# A-14732-40009.net
KiCad netlist of a schematic drawn in EAGLE
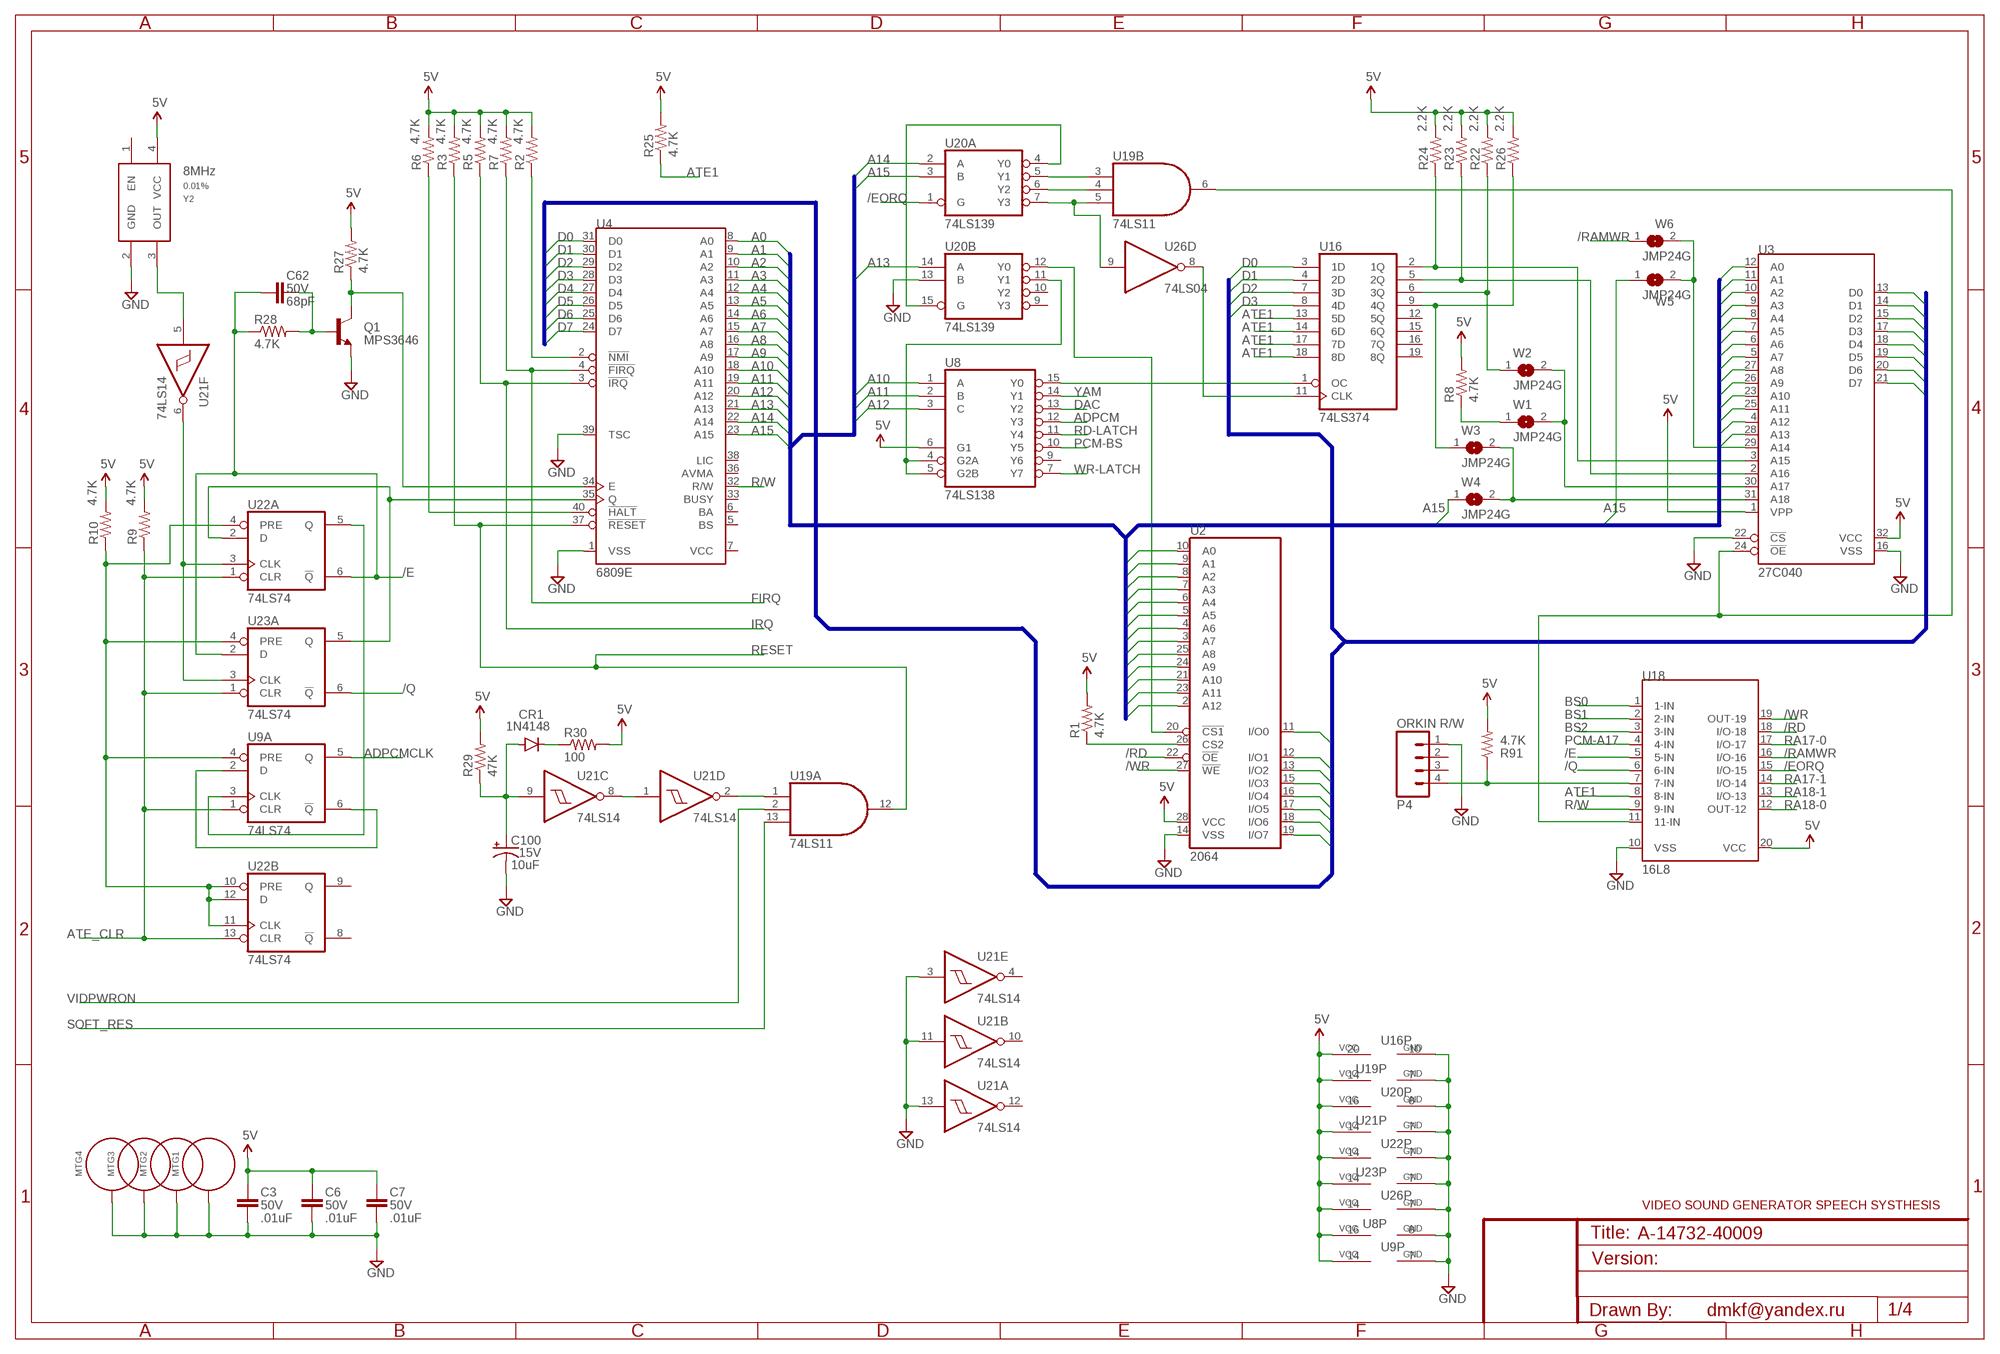
[diagram p0: schematic, sheet 1]
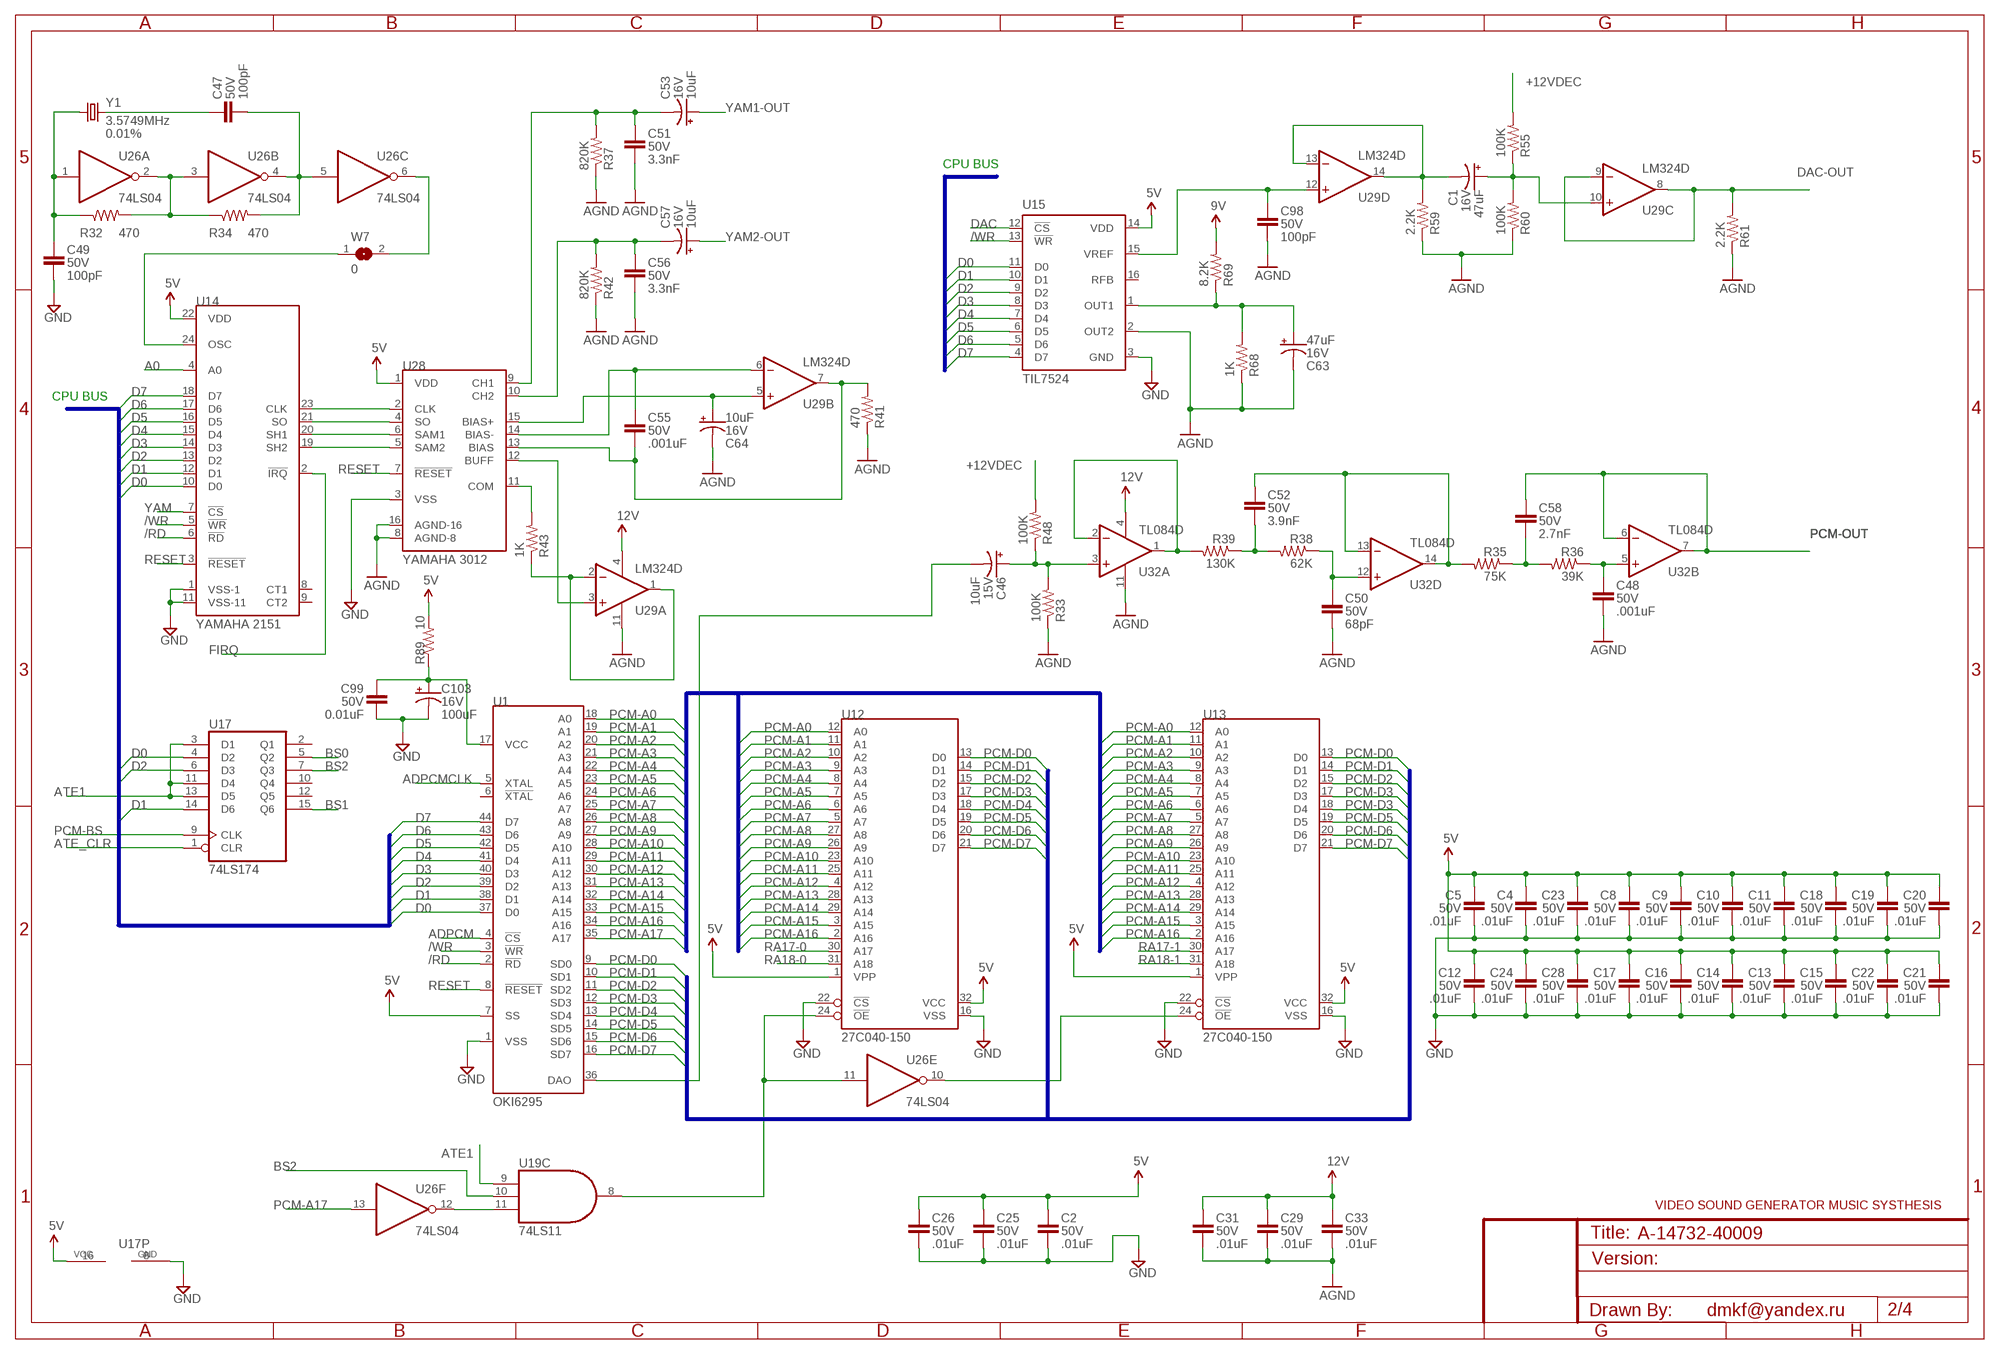
[diagram p1: schematic, sheet 2]
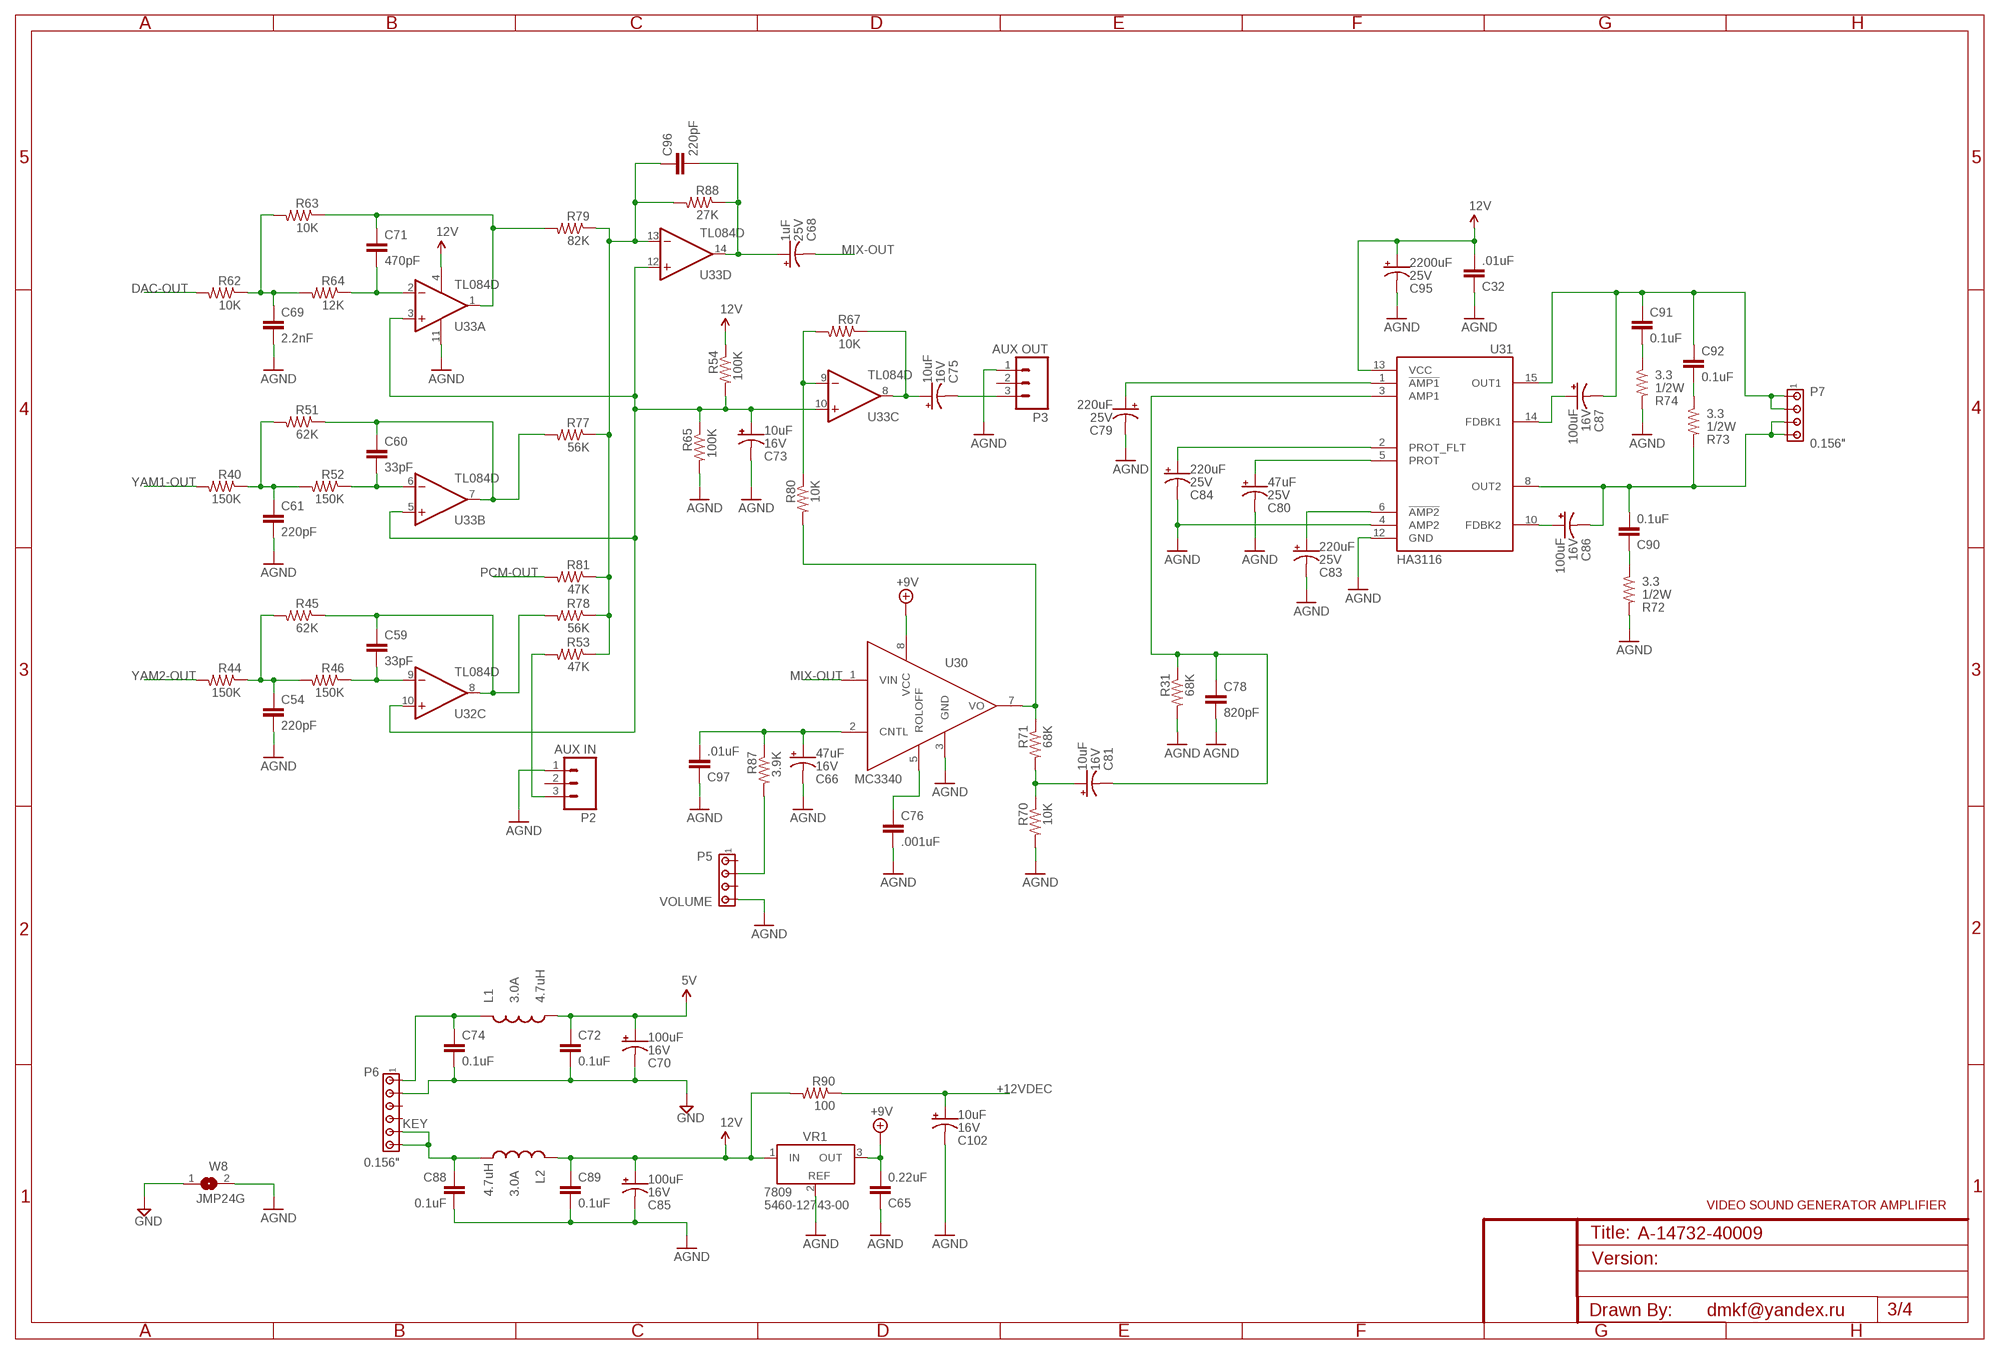
[diagram p2: schematic, sheet 3]
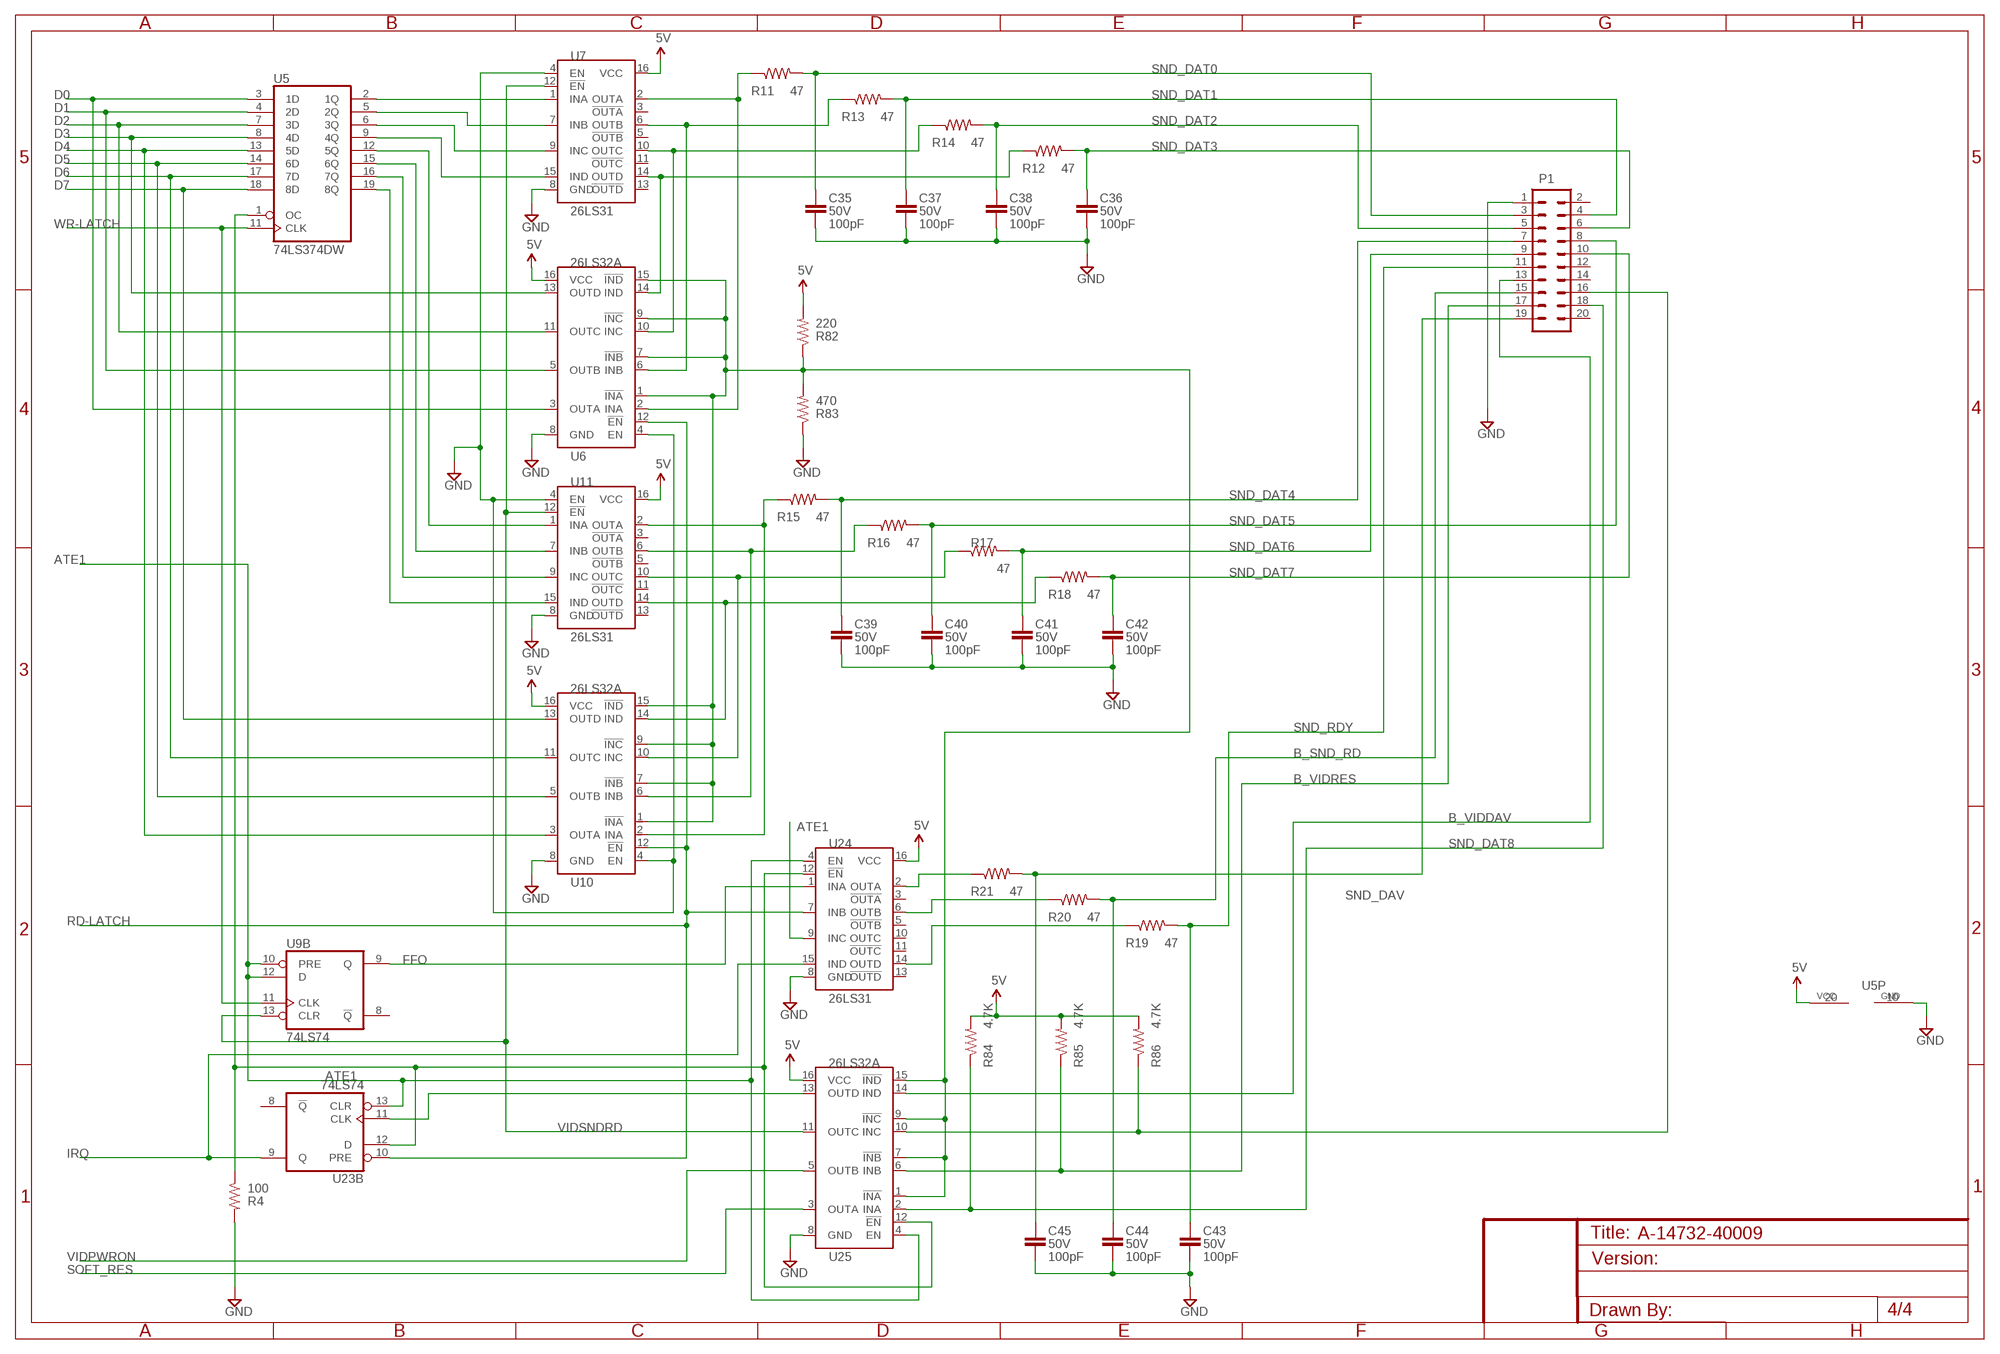
[diagram p3: schematic, sheet 4]

(export (version "E")
  (design (tool "Eeschema 10.0.6"))
  (components
    (comp (ref "C3")
      (value ".01uF")
      (footprint "eagle-import:1206-CAP")
      (fields (field (name "VOLTAGE") "50V"))
      (libsource (lib "eagle-import") (part "1.0UF50V10%(1206)"))
    )
    (comp (ref "C6")
      (value ".01uF")
      (footprint "eagle-import:1206-CAP")
      (fields (field (name "VOLTAGE") "50V"))
      (libsource (lib "eagle-import") (part "1.0UF50V10%(1206)"))
    )
    (comp (ref "C7")
      (value ".01uF")
      (footprint "eagle-import:1206-CAP")
      (fields (field (name "VOLTAGE") "50V"))
      (libsource (lib "eagle-import") (part "1.0UF50V10%(1206)"))
    )
    (comp (ref "C62")
      (value "68pF")
      (footprint "eagle-import:1206-CAP")
      (libsource (lib "eagle-import") (part "1.0UF50V10%(1206)"))
    )
    (comp (ref "C100")
      (value "10uF")
      (footprint "eagle-import:EIA3216")
      (libsource (lib "eagle-import") (part "10UF-16V-10%(TANT)"))
    )
    (comp (ref "CR1")
      (value "1N4148")
      (footprint "eagle-import:SMA-DIODE")
      (libsource (lib "eagle-import") (part "DIODESMA"))
    )
    (comp (ref "MTG1")
      (value "MTGHOLE")
      (footprint "eagle-import:STANDOFF-ELECTRICAL")
      (libsource (lib "eagle-import") (part "STANDOFF_ELECTRICAL"))
    )
    (comp (ref "MTG2")
      (value "MTGHOLE")
      (footprint "eagle-import:STANDOFF-ELECTRICAL")
      (libsource (lib "eagle-import") (part "STANDOFF_ELECTRICAL"))
    )
    (comp (ref "MTG3")
      (value "MTGHOLE")
      (footprint "eagle-import:STANDOFF-ELECTRICAL")
      (libsource (lib "eagle-import") (part "STANDOFF_ELECTRICAL"))
    )
    (comp (ref "MTG4")
      (value "MTGHOLE")
      (footprint "eagle-import:STANDOFF-ELECTRICAL")
      (libsource (lib "eagle-import") (part "STANDOFF_ELECTRICAL"))
    )
    (comp (ref "P4")
      (value "ORKIN R/W")
      (footprint "eagle-import:1X04_LONGPADS")
      (libsource (lib "eagle-import") (part "M04LONGPADS"))
    )
    (comp (ref "Q1")
      (value "MPS3646")
      (footprint "eagle-import:SOT23-3")
      (libsource (lib "eagle-import") (part "TRANSISTOR_NPNMMBT2222A"))
    )
    (comp (ref "R1")
      (value "4.7K")
      (footprint "eagle-import:R1206")
      (libsource (lib "eagle-import") (part "R-US_R1206"))
    )
    (comp (ref "R2")
      (value "4.7K")
      (footprint "eagle-import:R1206")
      (libsource (lib "eagle-import") (part "R-US_R1206"))
    )
    (comp (ref "R3")
      (value "4.7K")
      (footprint "eagle-import:R1206")
      (libsource (lib "eagle-import") (part "R-US_R1206"))
    )
    (comp (ref "R5")
      (value "4.7K")
      (footprint "eagle-import:R1206")
      (libsource (lib "eagle-import") (part "R-US_R1206"))
    )
    (comp (ref "R6")
      (value "4.7K")
      (footprint "eagle-import:R1206")
      (libsource (lib "eagle-import") (part "R-US_R1206"))
    )
    (comp (ref "R7")
      (value "4.7K")
      (footprint "eagle-import:R1206")
      (libsource (lib "eagle-import") (part "R-US_R1206"))
    )
    (comp (ref "R8")
      (value "4.7K")
      (footprint "eagle-import:R1206")
      (libsource (lib "eagle-import") (part "R-US_R1206"))
    )
    (comp (ref "R9")
      (value "4.7K")
      (footprint "eagle-import:R1206")
      (libsource (lib "eagle-import") (part "R-US_R1206"))
    )
    (comp (ref "R10")
      (value "4.7K")
      (footprint "eagle-import:R1206")
      (libsource (lib "eagle-import") (part "R-US_R1206"))
    )
    (comp (ref "R22")
      (value "2.2K")
      (footprint "eagle-import:R1206")
      (libsource (lib "eagle-import") (part "R-US_R1206"))
    )
    (comp (ref "R23")
      (value "2.2K")
      (footprint "eagle-import:R1206")
      (libsource (lib "eagle-import") (part "R-US_R1206"))
    )
    (comp (ref "R24")
      (value "2.2K")
      (footprint "eagle-import:R1206")
      (libsource (lib "eagle-import") (part "R-US_R1206"))
    )
    (comp (ref "R25")
      (value "4.7K")
      (footprint "eagle-import:R1206")
      (libsource (lib "eagle-import") (part "R-US_R1206"))
    )
    (comp (ref "R26")
      (value "2.2K")
      (footprint "eagle-import:R1206")
      (libsource (lib "eagle-import") (part "R-US_R1206"))
    )
    (comp (ref "R27")
      (value "4.7K")
      (footprint "eagle-import:R1206")
      (libsource (lib "eagle-import") (part "R-US_R1206"))
    )
    (comp (ref "R28")
      (value "4.7K")
      (footprint "eagle-import:R1206")
      (libsource (lib "eagle-import") (part "R-US_R1206"))
    )
    (comp (ref "R29")
      (value "47K")
      (footprint "eagle-import:R1206")
      (libsource (lib "eagle-import") (part "R-US_R1206"))
    )
    (comp (ref "R30")
      (value "100")
      (footprint "eagle-import:R1206")
      (libsource (lib "eagle-import") (part "R-US_R1206"))
    )
    (comp (ref "R91")
      (value "4.7K")
      (footprint "eagle-import:R1206")
      (libsource (lib "eagle-import") (part "R-US_R1206"))
    )
    (comp (ref "U2")
      (value "2064")
      (footprint "eagle-import:MS6264L")
      (libsource (lib "eagle-import") (part "MS6264L"))
    )
    (comp (ref "U3")
      (value "27C040")
      (footprint "eagle-import:27C040")
      (libsource (lib "eagle-import") (part "27C040"))
    )
    (comp (ref "U4")
      (value "6809E")
      (footprint "eagle-import:6809E")
      (libsource (lib "eagle-import") (part "6809E"))
    )
    (comp (ref "U8")
      (value "74LS138")
      (footprint "eagle-import:SO16")
      (libsource (lib "eagle-import") (part "74138DLS"))
    )
    (comp (ref "U9")
      (value "74LS74")
      (footprint "eagle-import:SO14")
      (libsource (lib "eagle-import") (part "7474DLS"))
    )
    (comp (ref "U16")
      (value "74LS374")
      (footprint "eagle-import:SO20W")
      (libsource (lib "eagle-import") (part "74374DWLS"))
    )
    (comp (ref "U18")
      (value "16L8")
      (footprint "eagle-import:16L8")
      (libsource (lib "eagle-import") (part "PAL16L8"))
    )
    (comp (ref "U19")
      (value "74LS11")
      (footprint "eagle-import:SO14")
      (libsource (lib "eagle-import") (part "7411DLS"))
    )
    (comp (ref "U20")
      (value "74LS139")
      (footprint "eagle-import:SO16")
      (libsource (lib "eagle-import") (part "74139DLS"))
    )
    (comp (ref "U21")
      (value "74LS14")
      (footprint "eagle-import:SO14")
      (libsource (lib "eagle-import") (part "7414DLS"))
    )
    (comp (ref "U22")
      (value "74LS74")
      (footprint "eagle-import:SO14")
      (libsource (lib "eagle-import") (part "7474DLS"))
    )
    (comp (ref "U23")
      (value "74LS74")
      (footprint "eagle-import:SO14")
      (libsource (lib "eagle-import") (part "7474DLS"))
    )
    (comp (ref "U26")
      (value "74LS04")
      (footprint "eagle-import:SO14")
      (libsource (lib "eagle-import") (part "7404DLS"))
    )
    (comp (ref "W1")
      (value "JMP24G")
      (footprint "eagle-import:SJ")
      (libsource (lib "eagle-import") (part "SJ"))
    )
    (comp (ref "W2")
      (value "JMP24G")
      (footprint "eagle-import:SJ")
      (libsource (lib "eagle-import") (part "SJ"))
    )
    (comp (ref "W3")
      (value "JMP24G")
      (footprint "eagle-import:SJ")
      (libsource (lib "eagle-import") (part "SJ"))
    )
    (comp (ref "W4")
      (value "JMP24G")
      (footprint "eagle-import:SJ")
      (libsource (lib "eagle-import") (part "SJ"))
    )
    (comp (ref "W5")
      (value "JMP24G")
      (footprint "eagle-import:SJ")
      (libsource (lib "eagle-import") (part "SJ"))
    )
    (comp (ref "W6")
      (value "JMP24G")
      (footprint "eagle-import:SJ")
      (libsource (lib "eagle-import") (part "SJ"))
    )
    (comp (ref "Y2")
      (value "8MHz")
      (footprint "eagle-import:CRYSTAL-OSC-SMD-5X3")
      (fields (field (name "TOLERANCE") "0.01%"))
      (libsource (lib "eagle-import") (part "OSCILLATOR5X3-PIN1-INDICATED"))
    )
    (comp (ref "C32")
      (value ".01uF")
      (footprint "eagle-import:1206-CAP")
      (fields (field (name "VOLTAGE") "50V"))
      (libsource (lib "eagle-import") (part "1.0UF50V10%(1206)"))
    )
    (comp (ref "C54")
      (value "220pF")
      (footprint "eagle-import:1206-CAP")
      (fields (field (name "VOLTAGE") "50V"))
      (libsource (lib "eagle-import") (part "1.0UF50V10%(1206)"))
    )
    (comp (ref "C59")
      (value "33pF")
      (footprint "eagle-import:1206-CAP")
      (fields (field (name "VOLTAGE") "50V"))
      (libsource (lib "eagle-import") (part "1.0UF50V10%(1206)"))
    )
    (comp (ref "C60")
      (value "33pF")
      (footprint "eagle-import:1206-CAP")
      (fields (field (name "VOLTAGE") "50V"))
      (libsource (lib "eagle-import") (part "1.0UF50V10%(1206)"))
    )
    (comp (ref "C61")
      (value "220pF")
      (footprint "eagle-import:1206-CAP")
      (fields (field (name "VOLTAGE") "50V"))
      (libsource (lib "eagle-import") (part "1.0UF50V10%(1206)"))
    )
    (comp (ref "C65")
      (value "0.22uF")
      (footprint "eagle-import:0805-CAP")
      (fields (field (name "VOLTAGE") "50V"))
      (libsource (lib "eagle-import") (part "0.33UF-50V-10%(0805)"))
    )
    (comp (ref "C66")
      (value "47uF")
      (footprint "eagle-import:NIC_10X10.5_CAP")
      (fields (field (name "VOLTAGE") "16V"))
      (libsource (lib "eagle-import") (part "100UF-63V-20%(ELECT)"))
    )
    (comp (ref "C68")
      (value "1uF")
      (footprint "eagle-import:NIC_10X10.5_CAP")
      (fields (field (name "VOLTAGE") "25V"))
      (libsource (lib "eagle-import") (part "100UF-63V-20%(ELECT)"))
    )
    (comp (ref "C69")
      (value "2.2nF")
      (footprint "eagle-import:1206-CAP")
      (fields (field (name "VOLTAGE") "50V"))
      (libsource (lib "eagle-import") (part "1.0UF50V10%(1206)"))
    )
    (comp (ref "C70")
      (value "100uF")
      (footprint "eagle-import:NIC_10X10.5_CAP")
      (fields (field (name "VOLTAGE") "16V"))
      (libsource (lib "eagle-import") (part "100UF-63V-20%(ELECT)"))
    )
    (comp (ref "C71")
      (value "470pF")
      (footprint "eagle-import:1206-CAP")
      (fields (field (name "VOLTAGE") "50V"))
      (libsource (lib "eagle-import") (part "1.0UF50V10%(1206)"))
    )
    (comp (ref "C72")
      (value "0.1uF")
      (footprint "eagle-import:1206-CAP")
      (fields (field (name "VOLTAGE") "50V"))
      (libsource (lib "eagle-import") (part "1.0UF50V10%(1206)"))
    )
    (comp (ref "C73")
      (value "10uF")
      (footprint "eagle-import:NIC_10X10.5_CAP")
      (fields (field (name "VOLTAGE") "16V"))
      (libsource (lib "eagle-import") (part "100UF-63V-20%(ELECT)"))
    )
    (comp (ref "C74")
      (value "0.1uF")
      (footprint "eagle-import:1206-CAP")
      (fields (field (name "VOLTAGE") "50V"))
      (libsource (lib "eagle-import") (part "1.0UF50V10%(1206)"))
    )
    (comp (ref "C75")
      (value "10uF")
      (footprint "eagle-import:NIC_10X10.5_CAP")
      (fields (field (name "VOLTAGE") "16V"))
      (libsource (lib "eagle-import") (part "100UF-63V-20%(ELECT)"))
    )
    (comp (ref "C76")
      (value ".001uF")
      (footprint "eagle-import:1206-CAP")
      (fields (field (name "VOLTAGE") "50V"))
      (libsource (lib "eagle-import") (part "1.0UF50V10%(1206)"))
    )
    (comp (ref "C78")
      (value "820pF")
      (footprint "eagle-import:1206-CAP")
      (fields (field (name "VOLTAGE") "50V"))
      (libsource (lib "eagle-import") (part "1.0UF50V10%(1206)"))
    )
    (comp (ref "C79")
      (value "220uF")
      (footprint "eagle-import:NIC_10X10.5_CAP")
      (fields (field (name "VOLTAGE") "25V"))
      (libsource (lib "eagle-import") (part "100UF-63V-20%(ELECT)"))
    )
    (comp (ref "C80")
      (value "47uF")
      (footprint "eagle-import:NIC_10X10.5_CAP")
      (fields (field (name "VOLTAGE") "25V"))
      (libsource (lib "eagle-import") (part "100UF-63V-20%(ELECT)"))
    )
    (comp (ref "C81")
      (value "10uF")
      (footprint "eagle-import:NIC_10X10.5_CAP")
      (fields (field (name "VOLTAGE") "16V"))
      (libsource (lib "eagle-import") (part "100UF-63V-20%(ELECT)"))
    )
    (comp (ref "C83")
      (value "220uF")
      (footprint "eagle-import:NIC_10X10.5_CAP")
      (fields (field (name "VOLTAGE") "25V"))
      (libsource (lib "eagle-import") (part "100UF-63V-20%(ELECT)"))
    )
    (comp (ref "C84")
      (value "220uF")
      (footprint "eagle-import:NIC_10X10.5_CAP")
      (fields (field (name "VOLTAGE") "25V"))
      (libsource (lib "eagle-import") (part "100UF-63V-20%(ELECT)"))
    )
    (comp (ref "C85")
      (value "100uF")
      (footprint "eagle-import:NIC_10X10.5_CAP")
      (fields (field (name "VOLTAGE") "16V"))
      (libsource (lib "eagle-import") (part "100UF-63V-20%(ELECT)"))
    )
    (comp (ref "C86")
      (value "100uF")
      (footprint "eagle-import:NIC_10X10.5_CAP")
      (fields (field (name "VOLTAGE") "16V"))
      (libsource (lib "eagle-import") (part "100UF-63V-20%(ELECT)"))
    )
    (comp (ref "C87")
      (value "100uF")
      (footprint "eagle-import:NIC_10X10.5_CAP")
      (fields (field (name "VOLTAGE") "16V"))
      (libsource (lib "eagle-import") (part "100UF-63V-20%(ELECT)"))
    )
    (comp (ref "C88")
      (value "0.1uF")
      (footprint "eagle-import:1206-CAP")
      (fields (field (name "VOLTAGE") "50V"))
      (libsource (lib "eagle-import") (part "1.0UF50V10%(1206)"))
    )
    (comp (ref "C89")
      (value "0.1uF")
      (footprint "eagle-import:1206-CAP")
      (fields (field (name "VOLTAGE") "50V"))
      (libsource (lib "eagle-import") (part "1.0UF50V10%(1206)"))
    )
    (comp (ref "C90")
      (value "0.1uF")
      (footprint "eagle-import:1206-CAP")
      (fields (field (name "VOLTAGE") "50V"))
      (libsource (lib "eagle-import") (part "1.0UF50V10%(1206)"))
    )
    (comp (ref "C91")
      (value "0.1uF")
      (footprint "eagle-import:1206-CAP")
      (fields (field (name "VOLTAGE") "50V"))
      (libsource (lib "eagle-import") (part "1.0UF50V10%(1206)"))
    )
    (comp (ref "C92")
      (value "0.1uF")
      (footprint "eagle-import:1206-CAP")
      (fields (field (name "VOLTAGE") "50V"))
      (libsource (lib "eagle-import") (part "1.0UF50V10%(1206)"))
    )
    (comp (ref "C95")
      (value "2200uF")
      (footprint "eagle-import:NIC_10X10.5_CAP")
      (fields (field (name "VOLTAGE") "25V"))
      (libsource (lib "eagle-import") (part "100UF-63V-20%(ELECT)"))
    )
    (comp (ref "C96")
      (value "220pF")
      (footprint "eagle-import:1206-CAP")
      (fields (field (name "VOLTAGE") "50V"))
      (libsource (lib "eagle-import") (part "1.0UF50V10%(1206)"))
    )
    (comp (ref "C97")
      (value ".01uF")
      (footprint "eagle-import:1206-CAP")
      (fields (field (name "VOLTAGE") "50V"))
      (libsource (lib "eagle-import") (part "1.0UF50V10%(1206)"))
    )
    (comp (ref "C102")
      (value "10uF")
      (footprint "eagle-import:NIC_10X10.5_CAP")
      (fields (field (name "VOLTAGE") "16V"))
      (libsource (lib "eagle-import") (part "100UF-63V-20%(ELECT)"))
    )
    (comp (ref "L1")
      (value "4.7uH")
      (footprint "eagle-import:NPI75C")
      (fields (field (name "CUR") "3.0A"))
      (libsource (lib "eagle-import") (part "INDUCTORNPI75"))
    )
    (comp (ref "L2")
      (value "4.7uH")
      (footprint "eagle-import:NPI75C")
      (fields (field (name "CURRENT") "3.0A"))
      (libsource (lib "eagle-import") (part "INDUCTORNPI75"))
    )
    (comp (ref "P2")
      (value "AUX IN")
      (footprint "eagle-import:1X03_LONGPADS")
      (libsource (lib "eagle-import") (part "M03LONGPADS"))
    )
    (comp (ref "P3")
      (value "AUX OUT")
      (footprint "eagle-import:1X03_LONGPADS")
      (libsource (lib "eagle-import") (part "M03LONGPADS"))
    )
    (comp (ref "P5")
      (value "VOLUME")
      (footprint "eagle-import:1X4MTA")
      (libsource (lib "eagle-import") (part "MTA04-156"))
    )
    (comp (ref "P6")
      (value "0.156\"")
      (footprint "eagle-import:1X6MTA")
      (libsource (lib "eagle-import") (part "MTA06-156"))
    )
    (comp (ref "P7")
      (value "0.156\"")
      (footprint "eagle-import:1X4MTA")
      (libsource (lib "eagle-import") (part "MTA04-156"))
    )
    (comp (ref "R31")
      (value "68K")
      (footprint "eagle-import:R1206")
      (libsource (lib "eagle-import") (part "R-US_R1206"))
    )
    (comp (ref "R40")
      (value "150K")
      (footprint "eagle-import:R1206")
      (libsource (lib "eagle-import") (part "R-US_R1206"))
    )
    (comp (ref "R44")
      (value "150K")
      (footprint "eagle-import:R1206")
      (libsource (lib "eagle-import") (part "R-US_R1206"))
    )
    (comp (ref "R45")
      (value "62K")
      (footprint "eagle-import:R1206")
      (libsource (lib "eagle-import") (part "R-US_R1206"))
    )
    (comp (ref "R46")
      (value "150K")
      (footprint "eagle-import:R1206")
      (libsource (lib "eagle-import") (part "R-US_R1206"))
    )
    (comp (ref "R51")
      (value "62K")
      (footprint "eagle-import:R1206")
      (libsource (lib "eagle-import") (part "R-US_R1206"))
    )
    (comp (ref "R52")
      (value "150K")
      (footprint "eagle-import:R1206")
      (libsource (lib "eagle-import") (part "R-US_R1206"))
    )
    (comp (ref "R53")
      (value "47K")
      (footprint "eagle-import:R1206")
      (libsource (lib "eagle-import") (part "R-US_R1206"))
    )
    (comp (ref "R54")
      (value "100K")
      (footprint "eagle-import:R1206")
      (libsource (lib "eagle-import") (part "R-US_R1206"))
    )
    (comp (ref "R62")
      (value "10K")
      (footprint "eagle-import:R1206")
      (libsource (lib "eagle-import") (part "R-US_R1206"))
    )
    (comp (ref "R63")
      (value "10K")
      (footprint "eagle-import:R1206")
      (libsource (lib "eagle-import") (part "R-US_R1206"))
    )
    (comp (ref "R64")
      (value "12K")
      (footprint "eagle-import:R1206")
      (libsource (lib "eagle-import") (part "R-US_R1206"))
    )
    (comp (ref "R65")
      (value "100K")
      (footprint "eagle-import:R1206")
      (libsource (lib "eagle-import") (part "R-US_R1206"))
    )
    (comp (ref "R67")
      (value "10K")
      (footprint "eagle-import:R1206")
      (libsource (lib "eagle-import") (part "R-US_R1206"))
    )
    (comp (ref "R70")
      (value "10K")
      (footprint "eagle-import:R1206")
      (libsource (lib "eagle-import") (part "R-US_R1206"))
    )
    (comp (ref "R71")
      (value "68K")
      (footprint "eagle-import:R1206")
      (libsource (lib "eagle-import") (part "R-US_R1206"))
    )
    (comp (ref "R72")
      (value "3.3")
      (footprint "eagle-import:R1206")
      (fields (field (name "POWER") "1/2W"))
      (libsource (lib "eagle-import") (part "R-US_R1206"))
    )
    (comp (ref "R73")
      (value "3.3")
      (footprint "eagle-import:R1206")
      (fields (field (name "POWER") "1/2W"))
      (libsource (lib "eagle-import") (part "R-US_R1206"))
    )
    (comp (ref "R74")
      (value "3.3")
      (footprint "eagle-import:R1206")
      (fields (field (name "POWER") "1/2W"))
      (libsource (lib "eagle-import") (part "R-US_R1206"))
    )
    (comp (ref "R77")
      (value "56K")
      (footprint "eagle-import:R1206")
      (libsource (lib "eagle-import") (part "R-US_R1206"))
    )
    (comp (ref "R78")
      (value "56K")
      (footprint "eagle-import:R1206")
      (libsource (lib "eagle-import") (part "R-US_R1206"))
    )
    (comp (ref "R79")
      (value "82K")
      (footprint "eagle-import:R1206")
      (libsource (lib "eagle-import") (part "R-US_R1206"))
    )
    (comp (ref "R80")
      (value "10K")
      (footprint "eagle-import:R1206")
      (libsource (lib "eagle-import") (part "R-US_R1206"))
    )
    (comp (ref "R81")
      (value "47K")
      (footprint "eagle-import:R1206")
      (libsource (lib "eagle-import") (part "R-US_R1206"))
    )
    (comp (ref "R87")
      (value "3.9K")
      (footprint "eagle-import:R1206")
      (libsource (lib "eagle-import") (part "R-US_R1206"))
    )
    (comp (ref "R88")
      (value "27K")
      (footprint "eagle-import:R1206")
      (libsource (lib "eagle-import") (part "R-US_R1206"))
    )
    (comp (ref "R90")
      (value "100")
      (footprint "eagle-import:R1206")
      (libsource (lib "eagle-import") (part "R-US_R1206"))
    )
    (comp (ref "U30")
      (value "MC3340")
      (footprint "eagle-import:MC3340")
      (libsource (lib "eagle-import") (part "MC3340"))
    )
    (comp (ref "U31")
      (value "HA3116")
      (footprint "eagle-import:ZIP15")
      (libsource (lib "eagle-import") (part "HA3116"))
    )
    (comp (ref "U32")
      (value "TL084D")
      (footprint "eagle-import:SO14")
      (libsource (lib "eagle-import") (part "TL084D"))
    )
    (comp (ref "U33")
      (value "TL084D")
      (footprint "eagle-import:SO14")
      (libsource (lib "eagle-import") (part "TL084D"))
    )
    (comp (ref "VR1")
      (value "7809")
      (footprint "eagle-import:7809-D2PAK")
      (fields (field (name "PARTNUMBER") "5460-12743-00"))
      (libsource (lib "eagle-import") (part "7809D2PAK"))
    )
    (comp (ref "W8")
      (value "JMP24G")
      (footprint "eagle-import:SJ")
      (libsource (lib "eagle-import") (part "SJ"))
    )
    (comp (ref "C35")
      (value "100pF")
      (footprint "eagle-import:1206-CAP")
      (fields (field (name "VOLTAGE") "50V"))
      (libsource (lib "eagle-import") (part "1.0UF50V10%(1206)"))
    )
    (comp (ref "C36")
      (value "100pF")
      (footprint "eagle-import:1206-CAP")
      (fields (field (name "VOLTAGE") "50V"))
      (libsource (lib "eagle-import") (part "1.0UF50V10%(1206)"))
    )
    (comp (ref "C37")
      (value "100pF")
      (footprint "eagle-import:1206-CAP")
      (fields (field (name "VOLTAGE") "50V"))
      (libsource (lib "eagle-import") (part "1.0UF50V10%(1206)"))
    )
    (comp (ref "C38")
      (value "100pF")
      (footprint "eagle-import:1206-CAP")
      (fields (field (name "VOLTAGE") "50V"))
      (libsource (lib "eagle-import") (part "1.0UF50V10%(1206)"))
    )
    (comp (ref "C39")
      (value "100pF")
      (footprint "eagle-import:1206-CAP")
      (fields (field (name "VOLTAGE") "50V"))
      (libsource (lib "eagle-import") (part "1.0UF50V10%(1206)"))
    )
    (comp (ref "C40")
      (value "100pF")
      (footprint "eagle-import:1206-CAP")
      (fields (field (name "VOLTAGE") "50V"))
      (libsource (lib "eagle-import") (part "1.0UF50V10%(1206)"))
    )
    (comp (ref "C41")
      (value "100pF")
      (footprint "eagle-import:1206-CAP")
      (fields (field (name "VOLTAGE") "50V"))
      (libsource (lib "eagle-import") (part "1.0UF50V10%(1206)"))
    )
    (comp (ref "C42")
      (value "100pF")
      (footprint "eagle-import:1206-CAP")
      (fields (field (name "VOLTAGE") "50V"))
      (libsource (lib "eagle-import") (part "1.0UF50V10%(1206)"))
    )
    (comp (ref "C43")
      (value "100pF")
      (footprint "eagle-import:1206-CAP")
      (fields (field (name "VOLTAGE") "50V"))
      (libsource (lib "eagle-import") (part "1.0UF50V10%(1206)"))
    )
    (comp (ref "C44")
      (value "100pF")
      (footprint "eagle-import:1206-CAP")
      (fields (field (name "VOLTAGE") "50V"))
      (libsource (lib "eagle-import") (part "1.0UF50V10%(1206)"))
    )
    (comp (ref "C45")
      (value "100pF")
      (footprint "eagle-import:1206-CAP")
      (fields (field (name "VOLTAGE") "50V"))
      (libsource (lib "eagle-import") (part "1.0UF50V10%(1206)"))
    )
    (comp (ref "P1")
      (value "M10X2ROUND_NOSILK")
      (footprint "eagle-import:2X10_ROUND_NOSILK")
      (libsource (lib "eagle-import") (part "M10X2ROUND_NOSILK"))
    )
    (comp (ref "R4")
      (value "100")
      (footprint "eagle-import:R1206")
      (libsource (lib "eagle-import") (part "R-US_R1206"))
    )
    (comp (ref "R11")
      (value "47")
      (footprint "eagle-import:R1206")
      (libsource (lib "eagle-import") (part "R-US_R1206"))
    )
    (comp (ref "R12")
      (value "47")
      (footprint "eagle-import:R1206")
      (libsource (lib "eagle-import") (part "R-US_R1206"))
    )
    (comp (ref "R13")
      (value "47")
      (footprint "eagle-import:R1206")
      (libsource (lib "eagle-import") (part "R-US_R1206"))
    )
    (comp (ref "R14")
      (value "47")
      (footprint "eagle-import:R1206")
      (libsource (lib "eagle-import") (part "R-US_R1206"))
    )
    (comp (ref "R15")
      (value "47")
      (footprint "eagle-import:R1206")
      (libsource (lib "eagle-import") (part "R-US_R1206"))
    )
    (comp (ref "R16")
      (value "47")
      (footprint "eagle-import:R1206")
      (libsource (lib "eagle-import") (part "R-US_R1206"))
    )
    (comp (ref "R17")
      (value "47")
      (footprint "eagle-import:R1206")
      (libsource (lib "eagle-import") (part "R-US_R1206"))
    )
    (comp (ref "R18")
      (value "47")
      (footprint "eagle-import:R1206")
      (libsource (lib "eagle-import") (part "R-US_R1206"))
    )
    (comp (ref "R19")
      (value "47")
      (footprint "eagle-import:R1206")
      (libsource (lib "eagle-import") (part "R-US_R1206"))
    )
    (comp (ref "R20")
      (value "47")
      (footprint "eagle-import:R1206")
      (libsource (lib "eagle-import") (part "R-US_R1206"))
    )
    (comp (ref "R21")
      (value "47")
      (footprint "eagle-import:R1206")
      (libsource (lib "eagle-import") (part "R-US_R1206"))
    )
    (comp (ref "R82")
      (value "220")
      (footprint "eagle-import:R1206")
      (libsource (lib "eagle-import") (part "R-US_R1206"))
    )
    (comp (ref "R83")
      (value "470")
      (footprint "eagle-import:R1206")
      (libsource (lib "eagle-import") (part "R-US_R1206"))
    )
    (comp (ref "R84")
      (value "4.7K")
      (footprint "eagle-import:R1206")
      (libsource (lib "eagle-import") (part "R-US_R1206"))
    )
    (comp (ref "R85")
      (value "4.7K")
      (footprint "eagle-import:R1206")
      (libsource (lib "eagle-import") (part "R-US_R1206"))
    )
    (comp (ref "R86")
      (value "4.7K")
      (footprint "eagle-import:R1206")
      (libsource (lib "eagle-import") (part "R-US_R1206"))
    )
    (comp (ref "U5")
      (value "74LS374DW")
      (footprint "eagle-import:SO20W")
      (libsource (lib "eagle-import") (part "74374DWLS"))
    )
    (comp (ref "U6")
      (value "26LS32A")
      (footprint "eagle-import:SO16")
      (libsource (lib "eagle-import") (part "26LS32A"))
    )
    (comp (ref "U7")
      (value "26LS31")
      (footprint "eagle-import:SO16")
      (libsource (lib "eagle-import") (part "26LS31"))
    )
    (comp (ref "U10")
      (value "26LS32A")
      (footprint "eagle-import:SO16")
      (libsource (lib "eagle-import") (part "26LS32A"))
    )
    (comp (ref "U11")
      (value "26LS31")
      (footprint "eagle-import:SO16")
      (libsource (lib "eagle-import") (part "26LS31"))
    )
    (comp (ref "U24")
      (value "26LS31")
      (footprint "eagle-import:SO16")
      (libsource (lib "eagle-import") (part "26LS31"))
    )
    (comp (ref "U25")
      (value "26LS32A")
      (footprint "eagle-import:SO16")
      (libsource (lib "eagle-import") (part "26LS32A"))
    )
    (comp (ref "C1")
      (value "47uF")
      (footprint "eagle-import:NIC_10X10.5_CAP")
      (fields (field (name "VOLTAGE") "16V"))
      (libsource (lib "eagle-import") (part "100UF-63V-20%(ELECT)"))
    )
    (comp (ref "C2")
      (value ".01uF")
      (footprint "eagle-import:1206-CAP")
      (fields (field (name "VOLTAGE") "50V"))
      (libsource (lib "eagle-import") (part "1.0UF50V10%(1206)"))
    )
    (comp (ref "C4")
      (value ".01uF")
      (footprint "eagle-import:1206-CAP")
      (fields (field (name "VOLTAGE") "50V"))
      (libsource (lib "eagle-import") (part "1.0UF50V10%(1206)"))
    )
    (comp (ref "C5")
      (value ".01uF")
      (footprint "eagle-import:1206-CAP")
      (fields (field (name "VOLTAGE") "50V"))
      (libsource (lib "eagle-import") (part "1.0UF50V10%(1206)"))
    )
    (comp (ref "C8")
      (value ".01uF")
      (footprint "eagle-import:1206-CAP")
      (fields (field (name "VOLTAGE") "50V"))
      (libsource (lib "eagle-import") (part "1.0UF50V10%(1206)"))
    )
    (comp (ref "C9")
      (value ".01uF")
      (footprint "eagle-import:1206-CAP")
      (fields (field (name "VOLTAGE") "50V"))
      (libsource (lib "eagle-import") (part "1.0UF50V10%(1206)"))
    )
    (comp (ref "C10")
      (value ".01uF")
      (footprint "eagle-import:1206-CAP")
      (fields (field (name "VOLTAGE") "50V"))
      (libsource (lib "eagle-import") (part "1.0UF50V10%(1206)"))
    )
    (comp (ref "C11")
      (value ".01uF")
      (footprint "eagle-import:1206-CAP")
      (fields (field (name "VOLTAGE") "50V"))
      (libsource (lib "eagle-import") (part "1.0UF50V10%(1206)"))
    )
    (comp (ref "C12")
      (value ".01uF")
      (footprint "eagle-import:1206-CAP")
      (fields (field (name "VOLTAGE") "50V"))
      (libsource (lib "eagle-import") (part "1.0UF50V10%(1206)"))
    )
    (comp (ref "C13")
      (value ".01uF")
      (footprint "eagle-import:1206-CAP")
      (fields (field (name "VOLTAGE") "50V"))
      (libsource (lib "eagle-import") (part "1.0UF50V10%(1206)"))
    )
    (comp (ref "C14")
      (value ".01uF")
      (footprint "eagle-import:1206-CAP")
      (fields (field (name "VOLTAGE") "50V"))
      (libsource (lib "eagle-import") (part "1.0UF50V10%(1206)"))
    )
    (comp (ref "C15")
      (value ".01uF")
      (footprint "eagle-import:1206-CAP")
      (fields (field (name "VOLTAGE") "50V"))
      (libsource (lib "eagle-import") (part "1.0UF50V10%(1206)"))
    )
    (comp (ref "C16")
      (value ".01uF")
      (footprint "eagle-import:1206-CAP")
      (fields (field (name "VOLTAGE") "50V"))
      (libsource (lib "eagle-import") (part "1.0UF50V10%(1206)"))
    )
    (comp (ref "C17")
      (value ".01uF")
      (footprint "eagle-import:1206-CAP")
      (fields (field (name "VOLTAGE") "50V"))
      (libsource (lib "eagle-import") (part "1.0UF50V10%(1206)"))
    )
    (comp (ref "C18")
      (value ".01uF")
      (footprint "eagle-import:1206-CAP")
      (fields (field (name "VOLTAGE") "50V"))
      (libsource (lib "eagle-import") (part "1.0UF50V10%(1206)"))
    )
    (comp (ref "C19")
      (value ".01uF")
      (footprint "eagle-import:1206-CAP")
      (fields (field (name "VOLTAGE") "50V"))
      (libsource (lib "eagle-import") (part "1.0UF50V10%(1206)"))
    )
    (comp (ref "C20")
      (value ".01uF")
      (footprint "eagle-import:1206-CAP")
      (fields (field (name "VOLTAGE") "50V"))
      (libsource (lib "eagle-import") (part "1.0UF50V10%(1206)"))
    )
    (comp (ref "C21")
      (value ".01uF")
      (footprint "eagle-import:1206-CAP")
      (fields (field (name "VOLTAGE") "50V"))
      (libsource (lib "eagle-import") (part "1.0UF50V10%(1206)"))
    )
    (comp (ref "C22")
      (value ".01uF")
      (footprint "eagle-import:1206-CAP")
      (fields (field (name "VOLTAGE") "50V"))
      (libsource (lib "eagle-import") (part "1.0UF50V10%(1206)"))
    )
    (comp (ref "C23")
      (value ".01uF")
      (footprint "eagle-import:1206-CAP")
      (fields (field (name "VOLTAGE") "50V"))
      (libsource (lib "eagle-import") (part "1.0UF50V10%(1206)"))
    )
    (comp (ref "C24")
      (value ".01uF")
      (footprint "eagle-import:1206-CAP")
      (fields (field (name "VOLTAGE") "50V"))
      (libsource (lib "eagle-import") (part "1.0UF50V10%(1206)"))
    )
    (comp (ref "C25")
      (value ".01uF")
      (footprint "eagle-import:1206-CAP")
      (fields (field (name "VOLTAGE") "50V"))
      (libsource (lib "eagle-import") (part "1.0UF50V10%(1206)"))
    )
    (comp (ref "C26")
      (value ".01uF")
      (footprint "eagle-import:1206-CAP")
      (fields (field (name "VOLTAGE") "50V"))
      (libsource (lib "eagle-import") (part "1.0UF50V10%(1206)"))
    )
    (comp (ref "C28")
      (value ".01uF")
      (footprint "eagle-import:1206-CAP")
      (fields (field (name "VOLTAGE") "50V"))
      (libsource (lib "eagle-import") (part "1.0UF50V10%(1206)"))
    )
    (comp (ref "C29")
      (value ".01uF")
      (footprint "eagle-import:1206-CAP")
      (fields (field (name "VOLTAGE") "50V"))
      (libsource (lib "eagle-import") (part "1.0UF50V10%(1206)"))
    )
    (comp (ref "C31")
      (value ".01uF")
      (footprint "eagle-import:1206-CAP")
      (fields (field (name "VOLTAGE") "50V"))
      (libsource (lib "eagle-import") (part "1.0UF50V10%(1206)"))
    )
    (comp (ref "C33")
      (value ".01uF")
      (footprint "eagle-import:1206-CAP")
      (fields (field (name "VOLTAGE") "50V"))
      (libsource (lib "eagle-import") (part "1.0UF50V10%(1206)"))
    )
    (comp (ref "C46")
      (value "10uF")
      (footprint "eagle-import:NIC_10X10.5_CAP")
      (fields (field (name "VOLTAGE") "15V"))
      (libsource (lib "eagle-import") (part "100UF-63V-20%(ELECT)"))
    )
    (comp (ref "C47")
      (value "100pF")
      (footprint "eagle-import:1206-CAP")
      (fields (field (name "VOLTAGE") "50V"))
      (libsource (lib "eagle-import") (part "1.0UF50V10%(1206)"))
    )
    (comp (ref "C48")
      (value ".001uF")
      (footprint "eagle-import:1206-CAP")
      (fields (field (name "VOLTAGE") "50V"))
      (libsource (lib "eagle-import") (part "1.0UF50V10%(1206)"))
    )
    (comp (ref "C49")
      (value "100pF")
      (footprint "eagle-import:1206-CAP")
      (fields (field (name "VOLTAGE") "50V"))
      (libsource (lib "eagle-import") (part "1.0UF50V10%(1206)"))
    )
    (comp (ref "C50")
      (value "68pF")
      (footprint "eagle-import:1206-CAP")
      (fields (field (name "VOLTAGE") "50V"))
      (libsource (lib "eagle-import") (part "1.0UF50V10%(1206)"))
    )
    (comp (ref "C51")
      (value "3.3nF")
      (footprint "eagle-import:1206-CAP")
      (fields (field (name "VOLTAGE") "50V"))
      (libsource (lib "eagle-import") (part "1.0UF50V10%(1206)"))
    )
    (comp (ref "C52")
      (value "3.9nF")
      (footprint "eagle-import:1206-CAP")
      (fields (field (name "VOLTAGE") "50V"))
      (libsource (lib "eagle-import") (part "1.0UF50V10%(1206)"))
    )
    (comp (ref "C53")
      (value "10uF")
      (footprint "eagle-import:NIC_10X10.5_CAP")
      (fields (field (name "VOLTAGE") "16V"))
      (libsource (lib "eagle-import") (part "100UF-63V-20%(ELECT)"))
    )
    (comp (ref "C55")
      (value ".001uF")
      (footprint "eagle-import:1206-CAP")
      (fields (field (name "VOLTAGE") "50V"))
      (libsource (lib "eagle-import") (part "1.0UF50V10%(1206)"))
    )
    (comp (ref "C56")
      (value "3.3nF")
      (footprint "eagle-import:1206-CAP")
      (fields (field (name "VOLTAGE") "50V"))
      (libsource (lib "eagle-import") (part "1.0UF50V10%(1206)"))
    )
    (comp (ref "C57")
      (value "10uF")
      (footprint "eagle-import:NIC_10X10.5_CAP")
      (fields (field (name "VOLTAGE") "16V"))
      (libsource (lib "eagle-import") (part "100UF-63V-20%(ELECT)"))
    )
    (comp (ref "C58")
      (value "2.7nF")
      (footprint "eagle-import:1206-CAP")
      (fields (field (name "VOLTAGE") "50V"))
      (libsource (lib "eagle-import") (part "1.0UF50V10%(1206)"))
    )
    (comp (ref "C63")
      (value "47uF")
      (footprint "eagle-import:NIC_10X10.5_CAP")
      (fields (field (name "VOLTAGE") "16V"))
      (libsource (lib "eagle-import") (part "100UF-63V-20%(ELECT)"))
    )
    (comp (ref "C64")
      (value "10uF")
      (footprint "eagle-import:NIC_10X10.5_CAP")
      (fields (field (name "VOLTAGE") "16V"))
      (libsource (lib "eagle-import") (part "100UF-63V-20%(ELECT)"))
    )
    (comp (ref "C98")
      (value "100pF")
      (footprint "eagle-import:1206-CAP")
      (fields (field (name "VOLTAGE") "50V"))
      (libsource (lib "eagle-import") (part "1.0UF50V10%(1206)"))
    )
    (comp (ref "C99")
      (value "0.01uF")
      (footprint "eagle-import:1206-CAP")
      (fields (field (name "VOLTAGE") "50V"))
      (libsource (lib "eagle-import") (part "1.0UF50V10%(1206)"))
    )
    (comp (ref "C103")
      (value "100uF")
      (footprint "eagle-import:NIC_10X10.5_CAP")
      (fields (field (name "VOLTAGE") "16V"))
      (libsource (lib "eagle-import") (part "100UF-63V-20%(ELECT)"))
    )
    (comp (ref "R32")
      (value "470")
      (footprint "eagle-import:R1206")
      (libsource (lib "eagle-import") (part "R-US_R1206"))
    )
    (comp (ref "R33")
      (value "100K")
      (footprint "eagle-import:R1206")
      (libsource (lib "eagle-import") (part "R-US_R1206"))
    )
    (comp (ref "R34")
      (value "470")
      (footprint "eagle-import:R1206")
      (libsource (lib "eagle-import") (part "R-US_R1206"))
    )
    (comp (ref "R35")
      (value "75K")
      (footprint "eagle-import:R1206")
      (libsource (lib "eagle-import") (part "R-US_R1206"))
    )
    (comp (ref "R36")
      (value "39K")
      (footprint "eagle-import:R1206")
      (libsource (lib "eagle-import") (part "R-US_R1206"))
    )
    (comp (ref "R37")
      (value "820K")
      (footprint "eagle-import:R1206")
      (libsource (lib "eagle-import") (part "R-US_R1206"))
    )
    (comp (ref "R38")
      (value "62K")
      (footprint "eagle-import:R1206")
      (libsource (lib "eagle-import") (part "R-US_R1206"))
    )
    (comp (ref "R39")
      (value "130K")
      (footprint "eagle-import:R1206")
      (libsource (lib "eagle-import") (part "R-US_R1206"))
    )
    (comp (ref "R41")
      (value "470")
      (footprint "eagle-import:R1206")
      (libsource (lib "eagle-import") (part "R-US_R1206"))
    )
    (comp (ref "R42")
      (value "820K")
      (footprint "eagle-import:R1206")
      (libsource (lib "eagle-import") (part "R-US_R1206"))
    )
    (comp (ref "R43")
      (value "1K")
      (footprint "eagle-import:R1206")
      (libsource (lib "eagle-import") (part "R-US_R1206"))
    )
    (comp (ref "R48")
      (value "100K")
      (footprint "eagle-import:R1206")
      (libsource (lib "eagle-import") (part "R-US_R1206"))
    )
    (comp (ref "R55")
      (value "100K")
      (footprint "eagle-import:R1206")
      (libsource (lib "eagle-import") (part "R-US_R1206"))
    )
    (comp (ref "R59")
      (value "2.2K")
      (footprint "eagle-import:R1206")
      (libsource (lib "eagle-import") (part "R-US_R1206"))
    )
    (comp (ref "R60")
      (value "100K")
      (footprint "eagle-import:R1206")
      (libsource (lib "eagle-import") (part "R-US_R1206"))
    )
    (comp (ref "R61")
      (value "2.2K")
      (footprint "eagle-import:R1206")
      (libsource (lib "eagle-import") (part "R-US_R1206"))
    )
    (comp (ref "R68")
      (value "1K")
      (footprint "eagle-import:R1206")
      (libsource (lib "eagle-import") (part "R-US_R1206"))
    )
    (comp (ref "R69")
      (value "8.2K")
      (footprint "eagle-import:R1206")
      (libsource (lib "eagle-import") (part "R-US_R1206"))
    )
    (comp (ref "R89")
      (value "10")
      (footprint "eagle-import:R1206")
      (libsource (lib "eagle-import") (part "R-US_R1206"))
    )
    (comp (ref "U1")
      (value "OKI6295")
      (footprint "eagle-import:OKI6295")
      (libsource (lib "eagle-import") (part "OKI6295"))
    )
    (comp (ref "U12")
      (value "27C040-150")
      (footprint "eagle-import:27C040")
      (libsource (lib "eagle-import") (part "27C040"))
    )
    (comp (ref "U13")
      (value "27C040-150")
      (footprint "eagle-import:27C040")
      (libsource (lib "eagle-import") (part "27C040"))
    )
    (comp (ref "U14")
      (value "YAMAHA 2151")
      (footprint "eagle-import:YM2151")
      (libsource (lib "eagle-import") (part "YM2151"))
    )
    (comp (ref "U15")
      (value "TIL7524")
      (footprint "eagle-import:SOIC16N")
      (fields (field (name "MF") "ALTERA CORPORATION") (field (name "MPN") "AD7524JRZ"))
      (libsource (lib "eagle-import") (part "AD7524RJ"))
    )
    (comp (ref "U17")
      (value "74LS174")
      (footprint "eagle-import:SO16")
      (libsource (lib "eagle-import") (part "74174DLS"))
    )
    (comp (ref "U28")
      (value "YAMAHA 3012")
      (footprint "eagle-import:YM3012")
      (libsource (lib "eagle-import") (part "YM3012"))
    )
    (comp (ref "U29")
      (value "LM324D")
      (footprint "eagle-import:SO14")
      (libsource (lib "eagle-import") (part "LM324D"))
    )
    (comp (ref "W7") (value "0") (footprint "eagle-import:SJ") (libsource (lib "eagle-import") (part "SJ")))
    (comp (ref "Y1")
      (value "3.5749MHz")
      (footprint "eagle-import:SM49")
      (fields (field (name "TOLERANCE") "0.01%"))
      (libsource (lib "eagle-import") (part "CRYSTALSM49"))
    )
  )
  (nets
    (net (code "1") (name "+9V") (class "Default")
      (node (ref "C65") (pin "2") (pinfunction "2_2") (pintype "passive"))
      (node (ref "U30") (pin "8") (pinfunction "VCC_8") (pintype "power_in"))
      (node (ref "VR1") (pin "3") (pinfunction "OUT_3") (pintype "passive"))
    )
    (net (code "2") (name "+12VDEC") (class "Default")
      (node (ref "C102") (pin "+") (pinfunction "+_+") (pintype "passive"))
      (node (ref "R48") (pin "2") (pinfunction "2_2") (pintype "passive"))
      (node (ref "R55") (pin "2") (pinfunction "2_2") (pintype "passive"))
      (node (ref "R90") (pin "1") (pinfunction "1_1") (pintype "passive"))
    )
    (net (code "3") (name "5V") (class "Default")
      (node (ref "C10") (pin "1") (pinfunction "1_1") (pintype "passive"))
      (node (ref "C11") (pin "1") (pinfunction "1_1") (pintype "passive"))
      (node (ref "C12") (pin "1") (pinfunction "1_1") (pintype "passive"))
      (node (ref "C13") (pin "1") (pinfunction "1_1") (pintype "passive"))
      (node (ref "C14") (pin "1") (pinfunction "1_1") (pintype "passive"))
      (node (ref "C15") (pin "1") (pinfunction "1_1") (pintype "passive"))
      (node (ref "C16") (pin "1") (pinfunction "1_1") (pintype "passive"))
      (node (ref "C17") (pin "1") (pinfunction "1_1") (pintype "passive"))
      (node (ref "C18") (pin "1") (pinfunction "1_1") (pintype "passive"))
      (node (ref "C19") (pin "1") (pinfunction "1_1") (pintype "passive"))
      (node (ref "C2") (pin "1") (pinfunction "1_1") (pintype "passive"))
      (node (ref "C20") (pin "1") (pinfunction "1_1") (pintype "passive"))
      (node (ref "C21") (pin "1") (pinfunction "1_1") (pintype "passive"))
      (node (ref "C22") (pin "1") (pinfunction "1_1") (pintype "passive"))
      (node (ref "C23") (pin "1") (pinfunction "1_1") (pintype "passive"))
      (node (ref "C24") (pin "1") (pinfunction "1_1") (pintype "passive"))
      (node (ref "C25") (pin "1") (pinfunction "1_1") (pintype "passive"))
      (node (ref "C26") (pin "1") (pinfunction "1_1") (pintype "passive"))
      (node (ref "C28") (pin "1") (pinfunction "1_1") (pintype "passive"))
      (node (ref "C3") (pin "1") (pinfunction "1_1") (pintype "passive"))
      (node (ref "C4") (pin "1") (pinfunction "1_1") (pintype "passive"))
      (node (ref "C5") (pin "1") (pinfunction "1_1") (pintype "passive"))
      (node (ref "C6") (pin "1") (pinfunction "1_1") (pintype "passive"))
      (node (ref "C7") (pin "1") (pinfunction "1_1") (pintype "passive"))
      (node (ref "C70") (pin "+") (pinfunction "+_+") (pintype "passive"))
      (node (ref "C72") (pin "1") (pinfunction "1_1") (pintype "passive"))
      (node (ref "C8") (pin "1") (pinfunction "1_1") (pintype "passive"))
      (node (ref "C9") (pin "1") (pinfunction "1_1") (pintype "passive"))
      (node (ref "L1") (pin "1") (pinfunction "1_1") (pintype "passive"))
      (node (ref "R1") (pin "2") (pinfunction "2_2") (pintype "passive"))
      (node (ref "R10") (pin "2") (pinfunction "2_2") (pintype "passive"))
      (node (ref "R2") (pin "2") (pinfunction "2_2") (pintype "passive"))
      (node (ref "R22") (pin "2") (pinfunction "2_2") (pintype "passive"))
      (node (ref "R23") (pin "2") (pinfunction "2_2") (pintype "passive"))
      (node (ref "R24") (pin "2") (pinfunction "2_2") (pintype "passive"))
      (node (ref "R25") (pin "2") (pinfunction "2_2") (pintype "passive"))
      (node (ref "R26") (pin "2") (pinfunction "2_2") (pintype "passive"))
      (node (ref "R27") (pin "2") (pinfunction "2_2") (pintype "passive"))
      (node (ref "R29") (pin "2") (pinfunction "2_2") (pintype "passive"))
      (node (ref "R3") (pin "2") (pinfunction "2_2") (pintype "passive"))
      (node (ref "R30") (pin "2") (pinfunction "2_2") (pintype "passive"))
      (node (ref "R5") (pin "2") (pinfunction "2_2") (pintype "passive"))
      (node (ref "R6") (pin "2") (pinfunction "2_2") (pintype "passive"))
      (node (ref "R69") (pin "2") (pinfunction "2_2") (pintype "passive"))
      (node (ref "R7") (pin "2") (pinfunction "2_2") (pintype "passive"))
      (node (ref "R8") (pin "2") (pinfunction "2_2") (pintype "passive"))
      (node (ref "R82") (pin "2") (pinfunction "2_2") (pintype "passive"))
      (node (ref "R84") (pin "2") (pinfunction "2_2") (pintype "passive"))
      (node (ref "R85") (pin "2") (pinfunction "2_2") (pintype "passive"))
      (node (ref "R86") (pin "2") (pinfunction "2_2") (pintype "passive"))
      (node (ref "R89") (pin "2") (pinfunction "2_2") (pintype "passive"))
      (node (ref "R9") (pin "2") (pinfunction "2_2") (pintype "passive"))
      (node (ref "R91") (pin "2") (pinfunction "2_2") (pintype "passive"))
      (node (ref "U1") (pin "7") (pinfunction "SS_7") (pintype "passive"))
      (node (ref "U10") (pin "16") (pinfunction "VCC_16") (pintype "power_in"))
      (node (ref "U11") (pin "16") (pinfunction "VCC_16") (pintype "power_in"))
      (node (ref "U12") (pin "1") (pinfunction "VPP_1") (pintype "passive"))
      (node (ref "U12") (pin "32") (pinfunction "VCC_32") (pintype "passive"))
      (node (ref "U13") (pin "1") (pinfunction "VPP_1") (pintype "passive"))
      (node (ref "U13") (pin "32") (pinfunction "VCC_32") (pintype "passive"))
      (node (ref "U14") (pin "22") (pinfunction "VDD_22") (pintype "passive"))
      (node (ref "U15") (pin "14") (pinfunction "VDD_14") (pintype "power_in"))
      (node (ref "U16") (pin "20") (pinfunction "VCC_20") (pintype "power_in"))
      (node (ref "U17") (pin "16") (pinfunction "VCC_16") (pintype "power_in"))
      (node (ref "U18") (pin "20") (pinfunction "VCC_20") (pintype "passive"))
      (node (ref "U19") (pin "14") (pinfunction "VCC_14") (pintype "power_in"))
      (node (ref "U2") (pin "28") (pinfunction "VCC_28") (pintype "power_in"))
      (node (ref "U20") (pin "16") (pinfunction "VCC_16") (pintype "power_in"))
      (node (ref "U21") (pin "14") (pinfunction "VCC_14") (pintype "power_in"))
      (node (ref "U22") (pin "14") (pinfunction "VCC_14") (pintype "power_in"))
      (node (ref "U23") (pin "14") (pinfunction "VCC_14") (pintype "power_in"))
      (node (ref "U24") (pin "16") (pinfunction "VCC_16") (pintype "power_in"))
      (node (ref "U25") (pin "16") (pinfunction "VCC_16") (pintype "power_in"))
      (node (ref "U26") (pin "14") (pinfunction "VCC_14") (pintype "power_in"))
      (node (ref "U28") (pin "1") (pinfunction "VDD_1") (pintype "passive"))
      (node (ref "U3") (pin "1") (pinfunction "VPP_1") (pintype "passive"))
      (node (ref "U3") (pin "32") (pinfunction "VCC_32") (pintype "passive"))
      (node (ref "U5") (pin "20") (pinfunction "VCC_20") (pintype "power_in"))
      (node (ref "U6") (pin "16") (pinfunction "VCC_16") (pintype "power_in"))
      (node (ref "U7") (pin "16") (pinfunction "VCC_16") (pintype "power_in"))
      (node (ref "U8") (pin "16") (pinfunction "VCC_16") (pintype "power_in"))
      (node (ref "U8") (pin "6") (pinfunction "G1_6") (pintype "input"))
      (node (ref "U9") (pin "14") (pinfunction "VCC_14") (pintype "power_in"))
      (node (ref "Y2") (pin "4") (pinfunction "VCC_4") (pintype "bidirectional"))
    )
    (net (code "4") (name "12V") (class "Default")
      (node (ref "C29") (pin "1") (pinfunction "1_1") (pintype "passive"))
      (node (ref "C31") (pin "1") (pinfunction "1_1") (pintype "passive"))
      (node (ref "C32") (pin "2") (pinfunction "2_2") (pintype "passive"))
      (node (ref "C33") (pin "1") (pinfunction "1_1") (pintype "passive"))
      (node (ref "C85") (pin "+") (pinfunction "+_+") (pintype "passive"))
      (node (ref "C89") (pin "1") (pinfunction "1_1") (pintype "passive"))
      (node (ref "C95") (pin "+") (pinfunction "+_+") (pintype "passive"))
      (node (ref "L2") (pin "2") (pinfunction "2_2") (pintype "passive"))
      (node (ref "R54") (pin "1") (pinfunction "1_1") (pintype "passive"))
      (node (ref "R90") (pin "2") (pinfunction "2_2") (pintype "passive"))
      (node (ref "U29") (pin "4") (pinfunction "V+_4") (pintype "power_in"))
      (node (ref "U31") (pin "13") (pinfunction "VCC_13") (pintype "power_in"))
      (node (ref "U32") (pin "4") (pinfunction "V+_4") (pintype "power_in"))
      (node (ref "U33") (pin "4") (pinfunction "V+_4") (pintype "power_in"))
      (node (ref "VR1") (pin "1") (pinfunction "IN_1") (pintype "input"))
    )
    (net (code "5") (name "A0") (class "Default")
      (node (ref "U14") (pin "4") (pinfunction "A0_4") (pintype "passive"))
      (node (ref "U2") (pin "10") (pinfunction "A0_10") (pintype "input"))
      (node (ref "U3") (pin "12") (pinfunction "A0_12") (pintype "passive"))
      (node (ref "U4") (pin "8") (pinfunction "A0_8") (pintype "passive"))
    )
    (net (code "6") (name "A1") (class "Default")
      (node (ref "U2") (pin "9") (pinfunction "A1_9") (pintype "input"))
      (node (ref "U3") (pin "11") (pinfunction "A1_11") (pintype "passive"))
      (node (ref "U4") (pin "9") (pinfunction "A1_9") (pintype "passive"))
    )
    (net (code "7") (name "A2") (class "Default")
      (node (ref "U2") (pin "8") (pinfunction "A2_8") (pintype "input"))
      (node (ref "U3") (pin "10") (pinfunction "A2_10") (pintype "passive"))
      (node (ref "U4") (pin "10") (pinfunction "A2_10") (pintype "passive"))
    )
    (net (code "8") (name "A3") (class "Default")
      (node (ref "U2") (pin "7") (pinfunction "A3_7") (pintype "input"))
      (node (ref "U3") (pin "9") (pinfunction "A3_9") (pintype "passive"))
      (node (ref "U4") (pin "11") (pinfunction "A3_11") (pintype "passive"))
    )
    (net (code "9") (name "A4") (class "Default")
      (node (ref "U2") (pin "6") (pinfunction "A4_6") (pintype "input"))
      (node (ref "U3") (pin "8") (pinfunction "A4_8") (pintype "passive"))
      (node (ref "U4") (pin "12") (pinfunction "A4_12") (pintype "passive"))
    )
    (net (code "10") (name "A5") (class "Default")
      (node (ref "U2") (pin "5") (pinfunction "A5_5") (pintype "input"))
      (node (ref "U3") (pin "7") (pinfunction "A5_7") (pintype "passive"))
      (node (ref "U4") (pin "13") (pinfunction "A5_13") (pintype "passive"))
    )
    (net (code "11") (name "A6") (class "Default")
      (node (ref "U2") (pin "4") (pinfunction "A6_4") (pintype "input"))
      (node (ref "U3") (pin "6") (pinfunction "A6_6") (pintype "passive"))
      (node (ref "U4") (pin "14") (pinfunction "A6_14") (pintype "passive"))
    )
    (net (code "12") (name "A7") (class "Default")
      (node (ref "U2") (pin "3") (pinfunction "A7_3") (pintype "input"))
      (node (ref "U3") (pin "5") (pinfunction "A7_5") (pintype "passive"))
      (node (ref "U4") (pin "15") (pinfunction "A7_15") (pintype "passive"))
    )
    (net (code "13") (name "A8") (class "Default")
      (node (ref "U2") (pin "25") (pinfunction "A8_25") (pintype "input"))
      (node (ref "U3") (pin "27") (pinfunction "A8_27") (pintype "passive"))
      (node (ref "U4") (pin "16") (pinfunction "A8_16") (pintype "passive"))
    )
    (net (code "14") (name "A9") (class "Default")
      (node (ref "U2") (pin "24") (pinfunction "A9_24") (pintype "input"))
      (node (ref "U3") (pin "26") (pinfunction "A9_26") (pintype "passive"))
      (node (ref "U4") (pin "17") (pinfunction "A9_17") (pintype "passive"))
    )
    (net (code "15") (name "A10") (class "Default")
      (node (ref "U2") (pin "21") (pinfunction "A10_21") (pintype "input"))
      (node (ref "U3") (pin "23") (pinfunction "A10_23") (pintype "passive"))
      (node (ref "U4") (pin "18") (pinfunction "A10_18") (pintype "passive"))
      (node (ref "U8") (pin "1") (pinfunction "A_1") (pintype "input"))
    )
    (net (code "16") (name "A11") (class "Default")
      (node (ref "U2") (pin "23") (pinfunction "A11_23") (pintype "input"))
      (node (ref "U3") (pin "25") (pinfunction "A11_25") (pintype "passive"))
      (node (ref "U4") (pin "19") (pinfunction "A11_19") (pintype "passive"))
      (node (ref "U8") (pin "2") (pinfunction "B_2") (pintype "input"))
    )
    (net (code "17") (name "A12") (class "Default")
      (node (ref "U2") (pin "2") (pinfunction "A12_2") (pintype "input"))
      (node (ref "U3") (pin "4") (pinfunction "A12_4") (pintype "passive"))
      (node (ref "U4") (pin "20") (pinfunction "A12_20") (pintype "passive"))
      (node (ref "U8") (pin "3") (pinfunction "C_3") (pintype "input"))
    )
    (net (code "18") (name "A13") (class "Default")
      (node (ref "U20") (pin "14") (pinfunction "A_14") (pintype "input"))
      (node (ref "U3") (pin "28") (pinfunction "A13_28") (pintype "passive"))
      (node (ref "U4") (pin "21") (pinfunction "A13_21") (pintype "passive"))
    )
    (net (code "19") (name "A14") (class "Default")
      (node (ref "U20") (pin "2") (pinfunction "A_2") (pintype "input"))
      (node (ref "U4") (pin "22") (pinfunction "A14_22") (pintype "passive"))
    )
    (net (code "20") (name "A15") (class "Default")
      (node (ref "U20") (pin "3") (pinfunction "B_3") (pintype "input"))
      (node (ref "U4") (pin "23") (pinfunction "A15_23") (pintype "passive"))
      (node (ref "W4") (pin "1") (pinfunction "1_1") (pintype "passive"))
      (node (ref "W5") (pin "1") (pinfunction "1_1") (pintype "passive"))
    )
    (net (code "21") (name "ADPCM") (class "Default")
      (node (ref "U1") (pin "4") (pinfunction "~{CS}_4") (pintype "passive"))
      (node (ref "U8") (pin "12") (pinfunction "Y3_12") (pintype "output"))
    )
    (net (code "22") (name "ADPCMCLK") (class "Default")
      (node (ref "U1") (pin "5") (pinfunction "XTAL_5") (pintype "passive"))
      (node (ref "U9") (pin "5") (pinfunction "Q_5") (pintype "output"))
    )
    (net (code "23") (name "AGND") (class "Default")
      (node (ref "C102") (pin "-") (pinfunction "-_-") (pintype "passive"))
      (node (ref "C29") (pin "2") (pinfunction "2_2") (pintype "passive"))
      (node (ref "C31") (pin "2") (pinfunction "2_2") (pintype "passive"))
      (node (ref "C32") (pin "1") (pinfunction "1_1") (pintype "passive"))
      (node (ref "C33") (pin "2") (pinfunction "2_2") (pintype "passive"))
      (node (ref "C48") (pin "2") (pinfunction "2_2") (pintype "passive"))
      (node (ref "C50") (pin "2") (pinfunction "2_2") (pintype "passive"))
      (node (ref "C51") (pin "2") (pinfunction "2_2") (pintype "passive"))
      (node (ref "C54") (pin "2") (pinfunction "2_2") (pintype "passive"))
      (node (ref "C56") (pin "2") (pinfunction "2_2") (pintype "passive"))
      (node (ref "C61") (pin "2") (pinfunction "2_2") (pintype "passive"))
      (node (ref "C63") (pin "-") (pinfunction "-_-") (pintype "passive"))
      (node (ref "C64") (pin "-") (pinfunction "-_-") (pintype "passive"))
      (node (ref "C65") (pin "1") (pinfunction "1_1") (pintype "passive"))
      (node (ref "C66") (pin "-") (pinfunction "-_-") (pintype "passive"))
      (node (ref "C69") (pin "2") (pinfunction "2_2") (pintype "passive"))
      (node (ref "C73") (pin "-") (pinfunction "-_-") (pintype "passive"))
      (node (ref "C76") (pin "2") (pinfunction "2_2") (pintype "passive"))
      (node (ref "C78") (pin "2") (pinfunction "2_2") (pintype "passive"))
      (node (ref "C79") (pin "-") (pinfunction "-_-") (pintype "passive"))
      (node (ref "C80") (pin "-") (pinfunction "-_-") (pintype "passive"))
      (node (ref "C83") (pin "-") (pinfunction "-_-") (pintype "passive"))
      (node (ref "C84") (pin "-") (pinfunction "-_-") (pintype "passive"))
      (node (ref "C85") (pin "-") (pinfunction "-_-") (pintype "passive"))
      (node (ref "C88") (pin "2") (pinfunction "2_2") (pintype "passive"))
      (node (ref "C89") (pin "2") (pinfunction "2_2") (pintype "passive"))
      (node (ref "C95") (pin "-") (pinfunction "-_-") (pintype "passive"))
      (node (ref "C97") (pin "1") (pinfunction "1_1") (pintype "passive"))
      (node (ref "C98") (pin "2") (pinfunction "2_2") (pintype "passive"))
      (node (ref "P2") (pin "1") (pinfunction "1_1") (pintype "passive"))
      (node (ref "P3") (pin "1") (pinfunction "1_1") (pintype "passive"))
      (node (ref "P5") (pin "4") (pinfunction "4_4") (pintype "passive"))
      (node (ref "R31") (pin "2") (pinfunction "2_2") (pintype "passive"))
      (node (ref "R33") (pin "1") (pinfunction "1_1") (pintype "passive"))
      (node (ref "R37") (pin "1") (pinfunction "1_1") (pintype "passive"))
      (node (ref "R41") (pin "1") (pinfunction "1_1") (pintype "passive"))
      (node (ref "R42") (pin "1") (pinfunction "1_1") (pintype "passive"))
      (node (ref "R59") (pin "1") (pinfunction "1_1") (pintype "passive"))
      (node (ref "R60") (pin "1") (pinfunction "1_1") (pintype "passive"))
      (node (ref "R61") (pin "1") (pinfunction "1_1") (pintype "passive"))
      (node (ref "R65") (pin "2") (pinfunction "2_2") (pintype "passive"))
      (node (ref "R68") (pin "1") (pinfunction "1_1") (pintype "passive"))
      (node (ref "R70") (pin "2") (pinfunction "2_2") (pintype "passive"))
      (node (ref "R72") (pin "2") (pinfunction "2_2") (pintype "passive"))
      (node (ref "R74") (pin "2") (pinfunction "2_2") (pintype "passive"))
      (node (ref "U15") (pin "2") (pinfunction "OUT2_2") (pintype "passive"))
      (node (ref "U28") (pin "16") (pinfunction "AGND-16_16") (pintype "passive"))
      (node (ref "U28") (pin "8") (pinfunction "AGND-8_8") (pintype "passive"))
      (node (ref "U29") (pin "11") (pinfunction "V-_11") (pintype "power_in"))
      (node (ref "U30") (pin "3") (pinfunction "GND_3") (pintype "power_in"))
      (node (ref "U31") (pin "12") (pinfunction "GND_12") (pintype "power_in"))
      (node (ref "U31") (pin "4") (pinfunction "AMP2_4") (pintype "passive"))
      (node (ref "U32") (pin "11") (pinfunction "V-_11") (pintype "power_in"))
      (node (ref "U33") (pin "11") (pinfunction "V-_11") (pintype "power_in"))
      (node (ref "VR1") (pin "2") (pinfunction "REF_2") (pintype "passive"))
      (node (ref "W8") (pin "2") (pinfunction "2_2") (pintype "passive"))
    )
    (net (code "24") (name "ATE1") (class "Default")
      (node (ref "R25") (pin "1") (pinfunction "1_1") (pintype "passive"))
      (node (ref "U16") (pin "13") (pinfunction "5D_13") (pintype "input"))
      (node (ref "U16") (pin "14") (pinfunction "6D_14") (pintype "input"))
      (node (ref "U16") (pin "17") (pinfunction "7D_17") (pintype "input"))
      (node (ref "U16") (pin "18") (pinfunction "8D_18") (pintype "input"))
      (node (ref "U17") (pin "11") (pinfunction "D4_11") (pintype "input"))
      (node (ref "U17") (pin "13") (pinfunction "D5_13") (pintype "input"))
      (node (ref "U17") (pin "3") (pinfunction "D1_3") (pintype "input"))
      (node (ref "U18") (pin "8") (pinfunction "8-IN_8") (pintype "passive"))
      (node (ref "U19") (pin "9") (pinfunction "I0_9") (pintype "input"))
      (node (ref "U23") (pin "13") (pinfunction "CLR_13") (pintype "input"))
      (node (ref "U24") (pin "4") (pinfunction "EN_4") (pintype "bidirectional"))
      (node (ref "U24") (pin "9") (pinfunction "INC_9") (pintype "input"))
      (node (ref "U25") (pin "4") (pinfunction "EN_4") (pintype "bidirectional"))
      (node (ref "U9") (pin "10") (pinfunction "PRE_10") (pintype "input"))
      (node (ref "U9") (pin "12") (pinfunction "D_12") (pintype "input"))
    )
    (net (code "25") (name "ATE_CLR") (class "Default")
      (node (ref "R9") (pin "1") (pinfunction "1_1") (pintype "passive"))
      (node (ref "U17") (pin "1") (pinfunction "CLR_1") (pintype "input"))
      (node (ref "U22") (pin "1") (pinfunction "CLR_1") (pintype "input"))
      (node (ref "U22") (pin "13") (pinfunction "CLR_13") (pintype "input"))
      (node (ref "U23") (pin "1") (pinfunction "CLR_1") (pintype "input"))
      (node (ref "U9") (pin "1") (pinfunction "CLR_1") (pintype "input"))
    )
    (net (code "26") (name "BS0") (class "Default")
      (node (ref "U17") (pin "5") (pinfunction "Q2_5") (pintype "output"))
      (node (ref "U18") (pin "1") (pinfunction "1-IN_1") (pintype "passive"))
    )
    (net (code "27") (name "BS1") (class "Default")
      (node (ref "U17") (pin "15") (pinfunction "Q6_15") (pintype "output"))
      (node (ref "U18") (pin "2") (pinfunction "2-IN_2") (pintype "passive"))
    )
    (net (code "28") (name "BS2") (class "Default")
      (node (ref "U17") (pin "7") (pinfunction "Q3_7") (pintype "output"))
      (node (ref "U18") (pin "3") (pinfunction "3-IN_3") (pintype "passive"))
      (node (ref "U19") (pin "10") (pinfunction "I1_10") (pintype "input"))
    )
    (net (code "29") (name "B_SND_RD") (class "Default")
      (node (ref "C44") (pin "1") (pinfunction "1_1") (pintype "passive"))
      (node (ref "P1") (pin "15") (pinfunction "15_15") (pintype "passive"))
      (node (ref "R20") (pin "2") (pinfunction "2_2") (pintype "passive"))
    )
    (net (code "30") (name "B_VIDDAV") (class "Default")
      (node (ref "P1") (pin "13") (pinfunction "13_13") (pintype "passive"))
      (node (ref "U25") (pin "14") (pinfunction "IND_14") (pintype "bidirectional"))
    )
    (net (code "31") (name "B_VIDRES") (class "Default")
      (node (ref "P1") (pin "17") (pinfunction "17_17") (pintype "passive"))
      (node (ref "R85") (pin "1") (pinfunction "1_1") (pintype "passive"))
      (node (ref "U25") (pin "6") (pinfunction "INB_6") (pintype "bidirectional"))
    )
    (net (code "32") (name "D0") (class "Default")
      (node (ref "U1") (pin "37") (pinfunction "D0_37") (pintype "passive"))
      (node (ref "U14") (pin "10") (pinfunction "D0_10") (pintype "passive"))
      (node (ref "U15") (pin "11") (pinfunction "D0_11") (pintype "input"))
      (node (ref "U16") (pin "3") (pinfunction "1D_3") (pintype "input"))
      (node (ref "U17") (pin "4") (pinfunction "D2_4") (pintype "input"))
      (node (ref "U2") (pin "11") (pinfunction "I/O0_11") (pintype "bidirectional"))
      (node (ref "U3") (pin "13") (pinfunction "D0_13") (pintype "passive"))
      (node (ref "U4") (pin "31") (pinfunction "D0_31") (pintype "passive"))
      (node (ref "U5") (pin "3") (pinfunction "1D_3") (pintype "input"))
      (node (ref "U6") (pin "3") (pinfunction "OUTA_3") (pintype "bidirectional"))
    )
    (net (code "33") (name "D1") (class "Default")
      (node (ref "U1") (pin "38") (pinfunction "D1_38") (pintype "passive"))
      (node (ref "U14") (pin "12") (pinfunction "D1_12") (pintype "passive"))
      (node (ref "U15") (pin "10") (pinfunction "D1_10") (pintype "input"))
      (node (ref "U16") (pin "4") (pinfunction "2D_4") (pintype "input"))
      (node (ref "U17") (pin "14") (pinfunction "D6_14") (pintype "input"))
      (node (ref "U2") (pin "12") (pinfunction "I/O1_12") (pintype "bidirectional"))
      (node (ref "U3") (pin "14") (pinfunction "D1_14") (pintype "passive"))
      (node (ref "U4") (pin "30") (pinfunction "D1_30") (pintype "passive"))
      (node (ref "U5") (pin "4") (pinfunction "2D_4") (pintype "input"))
      (node (ref "U6") (pin "5") (pinfunction "OUTB_5") (pintype "bidirectional"))
    )
    (net (code "34") (name "D2") (class "Default")
      (node (ref "U1") (pin "39") (pinfunction "D2_39") (pintype "passive"))
      (node (ref "U14") (pin "13") (pinfunction "D2_13") (pintype "passive"))
      (node (ref "U15") (pin "9") (pinfunction "D2_9") (pintype "input"))
      (node (ref "U16") (pin "7") (pinfunction "3D_7") (pintype "input"))
      (node (ref "U17") (pin "6") (pinfunction "D3_6") (pintype "input"))
      (node (ref "U2") (pin "13") (pinfunction "I/O2_13") (pintype "bidirectional"))
      (node (ref "U3") (pin "15") (pinfunction "D2_15") (pintype "passive"))
      (node (ref "U4") (pin "29") (pinfunction "D2_29") (pintype "passive"))
      (node (ref "U5") (pin "7") (pinfunction "3D_7") (pintype "input"))
      (node (ref "U6") (pin "11") (pinfunction "OUTC_11") (pintype "bidirectional"))
    )
    (net (code "35") (name "D3") (class "Default")
      (node (ref "U1") (pin "40") (pinfunction "D3_40") (pintype "passive"))
      (node (ref "U14") (pin "14") (pinfunction "D3_14") (pintype "passive"))
      (node (ref "U15") (pin "8") (pinfunction "D3_8") (pintype "input"))
      (node (ref "U16") (pin "8") (pinfunction "4D_8") (pintype "input"))
      (node (ref "U2") (pin "15") (pinfunction "I/O3_15") (pintype "bidirectional"))
      (node (ref "U3") (pin "17") (pinfunction "D3_17") (pintype "passive"))
      (node (ref "U4") (pin "28") (pinfunction "D3_28") (pintype "passive"))
      (node (ref "U5") (pin "8") (pinfunction "4D_8") (pintype "input"))
      (node (ref "U6") (pin "13") (pinfunction "OUTD_13") (pintype "bidirectional"))
    )
    (net (code "36") (name "D4") (class "Default")
      (node (ref "U1") (pin "41") (pinfunction "D4_41") (pintype "passive"))
      (node (ref "U10") (pin "3") (pinfunction "OUTA_3") (pintype "bidirectional"))
      (node (ref "U14") (pin "15") (pinfunction "D4_15") (pintype "passive"))
      (node (ref "U15") (pin "7") (pinfunction "D4_7") (pintype "input"))
      (node (ref "U2") (pin "16") (pinfunction "I/O4_16") (pintype "bidirectional"))
      (node (ref "U3") (pin "18") (pinfunction "D4_18") (pintype "passive"))
      (node (ref "U4") (pin "27") (pinfunction "D4_27") (pintype "passive"))
      (node (ref "U5") (pin "13") (pinfunction "5D_13") (pintype "input"))
    )
    (net (code "37") (name "D5") (class "Default")
      (node (ref "U1") (pin "42") (pinfunction "D5_42") (pintype "passive"))
      (node (ref "U10") (pin "5") (pinfunction "OUTB_5") (pintype "bidirectional"))
      (node (ref "U14") (pin "16") (pinfunction "D5_16") (pintype "passive"))
      (node (ref "U15") (pin "6") (pinfunction "D5_6") (pintype "input"))
      (node (ref "U2") (pin "17") (pinfunction "I/O5_17") (pintype "bidirectional"))
      (node (ref "U3") (pin "19") (pinfunction "D5_19") (pintype "passive"))
      (node (ref "U4") (pin "26") (pinfunction "D5_26") (pintype "passive"))
      (node (ref "U5") (pin "14") (pinfunction "6D_14") (pintype "input"))
    )
    (net (code "38") (name "D6") (class "Default")
      (node (ref "U1") (pin "43") (pinfunction "D6_43") (pintype "passive"))
      (node (ref "U10") (pin "11") (pinfunction "OUTC_11") (pintype "bidirectional"))
      (node (ref "U14") (pin "17") (pinfunction "D6_17") (pintype "passive"))
      (node (ref "U15") (pin "5") (pinfunction "D6_5") (pintype "input"))
      (node (ref "U2") (pin "18") (pinfunction "I/O6_18") (pintype "bidirectional"))
      (node (ref "U3") (pin "20") (pinfunction "D6_20") (pintype "passive"))
      (node (ref "U4") (pin "25") (pinfunction "D6_25") (pintype "passive"))
      (node (ref "U5") (pin "17") (pinfunction "7D_17") (pintype "input"))
    )
    (net (code "39") (name "D7") (class "Default")
      (node (ref "U1") (pin "44") (pinfunction "D7_44") (pintype "passive"))
      (node (ref "U10") (pin "13") (pinfunction "OUTD_13") (pintype "bidirectional"))
      (node (ref "U14") (pin "18") (pinfunction "D7_18") (pintype "passive"))
      (node (ref "U15") (pin "4") (pinfunction "D7_4") (pintype "input"))
      (node (ref "U2") (pin "19") (pinfunction "I/O7_19") (pintype "bidirectional"))
      (node (ref "U3") (pin "21") (pinfunction "D7_21") (pintype "passive"))
      (node (ref "U4") (pin "24") (pinfunction "D7_24") (pintype "passive"))
      (node (ref "U5") (pin "18") (pinfunction "8D_18") (pintype "input"))
    )
    (net (code "40") (name "DAC") (class "Default")
      (node (ref "U15") (pin "12") (pinfunction "~{CS}_12") (pintype "input"))
      (node (ref "U8") (pin "13") (pinfunction "Y2_13") (pintype "output"))
    )
    (net (code "41") (name "DAC-OUT") (class "Default")
      (node (ref "R61") (pin "2") (pinfunction "2_2") (pintype "passive"))
      (node (ref "R62") (pin "2") (pinfunction "2_2") (pintype "passive"))
      (node (ref "U29") (pin "8") (pinfunction "OUT_8") (pintype "output"))
      (node (ref "U29") (pin "9") (pinfunction "-IN_9") (pintype "input"))
    )
    (net (code "42") (name "FFO") (class "Default")
      (node (ref "U24") (pin "1") (pinfunction "INA_1") (pintype "input"))
      (node (ref "U9") (pin "9") (pinfunction "Q_9") (pintype "output"))
    )
    (net (code "43") (name "FIRQ") (class "Default")
      (node (ref "R7") (pin "1") (pinfunction "1_1") (pintype "passive"))
      (node (ref "U14") (pin "2") (pinfunction "~{IRQ}_2") (pintype "passive"))
      (node (ref "U4") (pin "4") (pinfunction "~{FIRQ}_4") (pintype "passive"))
    )
    (net (code "44") (name "GND") (class "Default")
      (node (ref "C10") (pin "2") (pinfunction "2_2") (pintype "passive"))
      (node (ref "C100") (pin "C") (pinfunction "-_C") (pintype "passive"))
      (node (ref "C103") (pin "-") (pinfunction "-_-") (pintype "passive"))
      (node (ref "C11") (pin "2") (pinfunction "2_2") (pintype "passive"))
      (node (ref "C12") (pin "2") (pinfunction "2_2") (pintype "passive"))
      (node (ref "C13") (pin "2") (pinfunction "2_2") (pintype "passive"))
      (node (ref "C14") (pin "2") (pinfunction "2_2") (pintype "passive"))
      (node (ref "C15") (pin "2") (pinfunction "2_2") (pintype "passive"))
      (node (ref "C16") (pin "2") (pinfunction "2_2") (pintype "passive"))
      (node (ref "C17") (pin "2") (pinfunction "2_2") (pintype "passive"))
      (node (ref "C18") (pin "2") (pinfunction "2_2") (pintype "passive"))
      (node (ref "C19") (pin "2") (pinfunction "2_2") (pintype "passive"))
      (node (ref "C2") (pin "2") (pinfunction "2_2") (pintype "passive"))
      (node (ref "C20") (pin "2") (pinfunction "2_2") (pintype "passive"))
      (node (ref "C21") (pin "2") (pinfunction "2_2") (pintype "passive"))
      (node (ref "C22") (pin "2") (pinfunction "2_2") (pintype "passive"))
      (node (ref "C23") (pin "2") (pinfunction "2_2") (pintype "passive"))
      (node (ref "C24") (pin "2") (pinfunction "2_2") (pintype "passive"))
      (node (ref "C25") (pin "2") (pinfunction "2_2") (pintype "passive"))
      (node (ref "C26") (pin "2") (pinfunction "2_2") (pintype "passive"))
      (node (ref "C28") (pin "2") (pinfunction "2_2") (pintype "passive"))
      (node (ref "C3") (pin "2") (pinfunction "2_2") (pintype "passive"))
      (node (ref "C35") (pin "2") (pinfunction "2_2") (pintype "passive"))
      (node (ref "C36") (pin "2") (pinfunction "2_2") (pintype "passive"))
      (node (ref "C37") (pin "2") (pinfunction "2_2") (pintype "passive"))
      (node (ref "C38") (pin "2") (pinfunction "2_2") (pintype "passive"))
      (node (ref "C39") (pin "2") (pinfunction "2_2") (pintype "passive"))
      (node (ref "C4") (pin "2") (pinfunction "2_2") (pintype "passive"))
      (node (ref "C40") (pin "2") (pinfunction "2_2") (pintype "passive"))
      (node (ref "C41") (pin "2") (pinfunction "2_2") (pintype "passive"))
      (node (ref "C42") (pin "2") (pinfunction "2_2") (pintype "passive"))
      (node (ref "C43") (pin "2") (pinfunction "2_2") (pintype "passive"))
      (node (ref "C44") (pin "2") (pinfunction "2_2") (pintype "passive"))
      (node (ref "C45") (pin "2") (pinfunction "2_2") (pintype "passive"))
      (node (ref "C49") (pin "2") (pinfunction "2_2") (pintype "passive"))
      (node (ref "C5") (pin "2") (pinfunction "2_2") (pintype "passive"))
      (node (ref "C6") (pin "2") (pinfunction "2_2") (pintype "passive"))
      (node (ref "C7") (pin "2") (pinfunction "2_2") (pintype "passive"))
      (node (ref "C70") (pin "-") (pinfunction "-_-") (pintype "passive"))
      (node (ref "C72") (pin "2") (pinfunction "2_2") (pintype "passive"))
      (node (ref "C74") (pin "2") (pinfunction "2_2") (pintype "passive"))
      (node (ref "C8") (pin "2") (pinfunction "2_2") (pintype "passive"))
      (node (ref "C9") (pin "2") (pinfunction "2_2") (pintype "passive"))
      (node (ref "C99") (pin "2") (pinfunction "2_2") (pintype "passive"))
      (node (ref "MTG1") (pin "P1") (pinfunction "P$1_P1") (pintype "bidirectional"))
      (node (ref "MTG2") (pin "P1") (pinfunction "P$1_P1") (pintype "bidirectional"))
      (node (ref "MTG3") (pin "P1") (pinfunction "P$1_P1") (pintype "bidirectional"))
      (node (ref "MTG4") (pin "P1") (pinfunction "P$1_P1") (pintype "bidirectional"))
      (node (ref "P1") (pin "1") (pinfunction "1_1") (pintype "passive"))
      (node (ref "P4") (pin "1") (pinfunction "1_1") (pintype "passive"))
      (node (ref "P6") (pin "2") (pinfunction "2_2") (pintype "passive"))
      (node (ref "Q1") (pin "2") (pinfunction "E_2") (pintype "passive"))
      (node (ref "R4") (pin "2") (pinfunction "2_2") (pintype "passive"))
      (node (ref "R83") (pin "1") (pinfunction "1_1") (pintype "passive"))
      (node (ref "U1") (pin "1") (pinfunction "VSS_1") (pintype "passive"))
      (node (ref "U10") (pin "4") (pinfunction "EN_4") (pintype "bidirectional"))
      (node (ref "U10") (pin "8") (pinfunction "GND_8") (pintype "power_in"))
      (node (ref "U11") (pin "4") (pinfunction "EN_4") (pintype "bidirectional"))
      (node (ref "U11") (pin "8") (pinfunction "GND_8") (pintype "power_in"))
      (node (ref "U12") (pin "16") (pinfunction "VSS_16") (pintype "passive"))
      (node (ref "U12") (pin "22") (pinfunction "~{CS}_22") (pintype "passive"))
      (node (ref "U13") (pin "16") (pinfunction "VSS_16") (pintype "passive"))
      (node (ref "U13") (pin "22") (pinfunction "~{CS}_22") (pintype "passive"))
      (node (ref "U14") (pin "1") (pinfunction "VSS-1_1") (pintype "passive"))
      (node (ref "U14") (pin "11") (pinfunction "VSS-11_11") (pintype "passive"))
      (node (ref "U15") (pin "3") (pinfunction "GND_3") (pintype "power_in"))
      (node (ref "U16") (pin "10") (pinfunction "GND_10") (pintype "power_in"))
      (node (ref "U17") (pin "8") (pinfunction "GND_8") (pintype "power_in"))
      (node (ref "U18") (pin "10") (pinfunction "VSS_10") (pintype "passive"))
      (node (ref "U19") (pin "7") (pinfunction "GND_7") (pintype "power_in"))
      (node (ref "U2") (pin "14") (pinfunction "VSS_14") (pintype "power_in"))
      (node (ref "U20") (pin "13") (pinfunction "B_13") (pintype "input"))
      (node (ref "U20") (pin "8") (pinfunction "GND_8") (pintype "power_in"))
      (node (ref "U21") (pin "11") (pinfunction "I_11") (pintype "input"))
      (node (ref "U21") (pin "13") (pinfunction "I_13") (pintype "input"))
      (node (ref "U21") (pin "3") (pinfunction "I_3") (pintype "input"))
      (node (ref "U21") (pin "7") (pinfunction "GND_7") (pintype "power_in"))
      (node (ref "U22") (pin "7") (pinfunction "GND_7") (pintype "power_in"))
      (node (ref "U23") (pin "7") (pinfunction "GND_7") (pintype "power_in"))
      (node (ref "U24") (pin "8") (pinfunction "GND_8") (pintype "power_in"))
      (node (ref "U25") (pin "8") (pinfunction "GND_8") (pintype "power_in"))
      (node (ref "U26") (pin "7") (pinfunction "GND_7") (pintype "power_in"))
      (node (ref "U28") (pin "3") (pinfunction "VSS_3") (pintype "passive"))
      (node (ref "U3") (pin "16") (pinfunction "VSS_16") (pintype "passive"))
      (node (ref "U3") (pin "22") (pinfunction "~{CS}_22") (pintype "passive"))
      (node (ref "U4") (pin "1") (pinfunction "VSS_1") (pintype "passive"))
      (node (ref "U4") (pin "39") (pinfunction "TSC_39") (pintype "passive"))
      (node (ref "U5") (pin "10") (pinfunction "GND_10") (pintype "power_in"))
      (node (ref "U6") (pin "4") (pinfunction "EN_4") (pintype "bidirectional"))
      (node (ref "U6") (pin "8") (pinfunction "GND_8") (pintype "power_in"))
      (node (ref "U7") (pin "4") (pinfunction "EN_4") (pintype "bidirectional"))
      (node (ref "U7") (pin "8") (pinfunction "GND_8") (pintype "power_in"))
      (node (ref "U8") (pin "8") (pinfunction "GND_8") (pintype "power_in"))
      (node (ref "U9") (pin "7") (pinfunction "GND_7") (pintype "power_in"))
      (node (ref "W8") (pin "1") (pinfunction "1_1") (pintype "passive"))
      (node (ref "Y2") (pin "2") (pinfunction "GND_2") (pintype "bidirectional"))
    )
    (net (code "45") (name "IRQ") (class "Default")
      (node (ref "R5") (pin "1") (pinfunction "1_1") (pintype "passive"))
      (node (ref "U23") (pin "9") (pinfunction "Q_9") (pintype "output"))
      (node (ref "U24") (pin "15") (pinfunction "IND_15") (pintype "input"))
      (node (ref "U4") (pin "3") (pinfunction "~{IRQ}_3") (pintype "passive"))
    )
    (net (code "46") (name "MIX-OUT") (class "Default")
      (node (ref "C68") (pin "-") (pinfunction "-_-") (pintype "passive"))
      (node (ref "U30") (pin "1") (pinfunction "VIN_1") (pintype "bidirectional"))
    )
    (net (code "47") (name "Net-(C47-Pad1)") (class "Default")
      (node (ref "C47") (pin "1") (pinfunction "1_1") (pintype "passive"))
      (node (ref "Y1") (pin "2") (pinfunction "2_2") (pintype "passive"))
    )
    (net (code "48") (name "Net-(C52-Pad2)") (class "Default")
      (node (ref "C52") (pin "2") (pinfunction "2_2") (pintype "passive"))
      (node (ref "R38") (pin "2") (pinfunction "2_2") (pintype "passive"))
      (node (ref "R39") (pin "1") (pinfunction "1_1") (pintype "passive"))
    )
    (net (code "49") (name "Net-(C54-Pad1)") (class "Default")
      (node (ref "C54") (pin "1") (pinfunction "1_1") (pintype "passive"))
      (node (ref "R44") (pin "1") (pinfunction "1_1") (pintype "passive"))
      (node (ref "R45") (pin "2") (pinfunction "2_2") (pintype "passive"))
      (node (ref "R46") (pin "2") (pinfunction "2_2") (pintype "passive"))
    )
    (net (code "50") (name "Net-(C58-Pad2)") (class "Default")
      (node (ref "C58") (pin "2") (pinfunction "2_2") (pintype "passive"))
      (node (ref "R35") (pin "1") (pinfunction "1_1") (pintype "passive"))
      (node (ref "R36") (pin "2") (pinfunction "2_2") (pintype "passive"))
    )
    (net (code "51") (name "Net-(C61-Pad1)") (class "Default")
      (node (ref "C61") (pin "1") (pinfunction "1_1") (pintype "passive"))
      (node (ref "R40") (pin "1") (pinfunction "1_1") (pintype "passive"))
      (node (ref "R51") (pin "2") (pinfunction "2_2") (pintype "passive"))
      (node (ref "R52") (pin "2") (pinfunction "2_2") (pintype "passive"))
    )
    (net (code "52") (name "Net-(C69-Pad1)") (class "Default")
      (node (ref "C69") (pin "1") (pinfunction "1_1") (pintype "passive"))
      (node (ref "R62") (pin "1") (pinfunction "1_1") (pintype "passive"))
      (node (ref "R63") (pin "2") (pinfunction "2_2") (pintype "passive"))
      (node (ref "R64") (pin "2") (pinfunction "2_2") (pintype "passive"))
    )
    (net (code "53") (name "Net-(C74-Pad1)") (class "Default")
      (node (ref "C74") (pin "1") (pinfunction "1_1") (pintype "passive"))
      (node (ref "L1") (pin "2") (pinfunction "2_2") (pintype "passive"))
      (node (ref "P6") (pin "1") (pinfunction "1_1") (pintype "passive"))
    )
    (net (code "54") (name "Net-(C75-Pad-)") (class "Default")
      (node (ref "C75") (pin "-") (pinfunction "-_-") (pintype "passive"))
      (node (ref "P3") (pin "3") (pinfunction "3_3") (pintype "passive"))
    )
    (net (code "55") (name "Net-(C81-Pad+)") (class "Default")
      (node (ref "C81") (pin "+") (pinfunction "+_+") (pintype "passive"))
      (node (ref "R70") (pin "1") (pinfunction "1_1") (pintype "passive"))
      (node (ref "R71") (pin "2") (pinfunction "2_2") (pintype "passive"))
    )
    (net (code "56") (name "Net-(C88-Pad1)") (class "Default")
      (node (ref "C88") (pin "1") (pinfunction "1_1") (pintype "passive"))
      (node (ref "L2") (pin "1") (pinfunction "1_1") (pintype "passive"))
      (node (ref "P6") (pin "5") (pinfunction "5_5") (pintype "passive"))
      (node (ref "P6") (pin "6") (pinfunction "6_6") (pintype "passive"))
    )
    (net (code "57") (name "Net-(C90-Pad1)") (class "Default")
      (node (ref "C90") (pin "1") (pinfunction "1_1") (pintype "passive"))
      (node (ref "R72") (pin "1") (pinfunction "1_1") (pintype "passive"))
    )
    (net (code "58") (name "Net-(C91-Pad2)") (class "Default")
      (node (ref "C91") (pin "2") (pinfunction "2_2") (pintype "passive"))
      (node (ref "R74") (pin "1") (pinfunction "1_1") (pintype "passive"))
    )
    (net (code "59") (name "Net-(C92-Pad2)") (class "Default")
      (node (ref "C92") (pin "2") (pinfunction "2_2") (pintype "passive"))
      (node (ref "R73") (pin "1") (pinfunction "1_1") (pintype "passive"))
    )
    (net (code "60") (name "Net-(C100-+)") (class "Default")
      (node (ref "C100") (pin "A") (pinfunction "+_A") (pintype "passive"))
      (node (ref "CR1") (pin "A") (pinfunction "A_A") (pintype "passive"))
      (node (ref "R29") (pin "1") (pinfunction "1_1") (pintype "passive"))
      (node (ref "U21") (pin "9") (pinfunction "I_9") (pintype "input"))
    )
    (net (code "61") (name "Net-(CR1-PadC)") (class "Default")
      (node (ref "CR1") (pin "C") (pinfunction "C_C") (pintype "passive"))
      (node (ref "R30") (pin "1") (pinfunction "1_1") (pintype "passive"))
    )
    (net (code "62") (name "Net-(P2-Pad3)") (class "Default")
      (node (ref "P2") (pin "3") (pinfunction "3_3") (pintype "passive"))
      (node (ref "R53") (pin "2") (pinfunction "2_2") (pintype "passive"))
    )
    (net (code "63") (name "Net-(P5-Pad2)") (class "Default")
      (node (ref "P5") (pin "2") (pinfunction "2_2") (pintype "passive"))
      (node (ref "R87") (pin "2") (pinfunction "2_2") (pintype "passive"))
    )
    (net (code "64") (name "Net-(Q1-B)") (class "Default")
      (node (ref "C62") (pin "2") (pinfunction "2_2") (pintype "passive"))
      (node (ref "Q1") (pin "1") (pinfunction "B_1") (pintype "passive"))
      (node (ref "R28") (pin "2") (pinfunction "2_2") (pintype "passive"))
    )
    (net (code "65") (name "Net-(Q1-C)") (class "Default")
      (node (ref "Q1") (pin "3") (pinfunction "C_3") (pintype "passive"))
      (node (ref "R27") (pin "1") (pinfunction "1_1") (pintype "passive"))
      (node (ref "U4") (pin "34") (pinfunction "E_34") (pintype "passive"))
    )
    (net (code "66") (name "Net-(R8-Pad1)") (class "Default")
      (node (ref "R8") (pin "1") (pinfunction "1_1") (pintype "passive"))
      (node (ref "W1") (pin "1") (pinfunction "1_1") (pintype "passive"))
    )
    (net (code "67") (name "Net-(U1-DAO)") (class "Default")
      (node (ref "C46") (pin "-") (pinfunction "-_-") (pintype "passive"))
      (node (ref "U1") (pin "36") (pinfunction "DAO_36") (pintype "passive"))
    )
    (net (code "68") (name "Net-(U1-VCC)") (class "Default")
      (node (ref "C103") (pin "+") (pinfunction "+_+") (pintype "passive"))
      (node (ref "C99") (pin "1") (pinfunction "1_1") (pintype "passive"))
      (node (ref "R89") (pin "1") (pinfunction "1_1") (pintype "passive"))
      (node (ref "U1") (pin "17") (pinfunction "VCC_17") (pintype "passive"))
    )
    (net (code "69") (name "Net-(U2-CS2)") (class "Default")
      (node (ref "R1") (pin "1") (pinfunction "1_1") (pintype "passive"))
      (node (ref "U2") (pin "26") (pinfunction "CS2_26") (pintype "input"))
    )
    (net (code "70") (name "Net-(U2-~{CS1})") (class "Default")
      (node (ref "U2") (pin "20") (pinfunction "~{CS1}_20") (pintype "input"))
      (node (ref "U20") (pin "12") (pinfunction "Y0_12") (pintype "output"))
    )
    (net (code "71") (name "Net-(U3-A14)") (class "Default")
      (node (ref "U3") (pin "29") (pinfunction "A14_29") (pintype "passive"))
      (node (ref "W5") (pin "2") (pinfunction "2_2") (pintype "passive"))
      (node (ref "W6") (pin "2") (pinfunction "2_2") (pintype "passive"))
    )
    (net (code "72") (name "Net-(U3-A17)") (class "Default")
      (node (ref "U3") (pin "30") (pinfunction "A17_30") (pintype "passive"))
      (node (ref "W1") (pin "2") (pinfunction "2_2") (pintype "passive"))
      (node (ref "W2") (pin "2") (pinfunction "2_2") (pintype "passive"))
    )
    (net (code "73") (name "Net-(U3-A18)") (class "Default")
      (node (ref "U3") (pin "31") (pinfunction "A18_31") (pintype "passive"))
      (node (ref "W3") (pin "2") (pinfunction "2_2") (pintype "passive"))
      (node (ref "W4") (pin "2") (pinfunction "2_2") (pintype "passive"))
    )
    (net (code "74") (name "Net-(U4-~{HALT})") (class "Default")
      (node (ref "R6") (pin "1") (pinfunction "1_1") (pintype "passive"))
      (node (ref "U4") (pin "40") (pinfunction "~{HALT}_40") (pintype "passive"))
    )
    (net (code "75") (name "Net-(U4-~{NMI})") (class "Default")
      (node (ref "R2") (pin "1") (pinfunction "1_1") (pintype "passive"))
      (node (ref "U4") (pin "2") (pinfunction "~{NMI}_2") (pintype "passive"))
    )
    (net (code "76") (name "Net-(U5A-1Q)") (class "Default")
      (node (ref "U5") (pin "2") (pinfunction "1Q_2") (pintype "tri_state"))
      (node (ref "U7") (pin "1") (pinfunction "INA_1") (pintype "input"))
    )
    (net (code "77") (name "Net-(U5A-2Q)") (class "Default")
      (node (ref "U5") (pin "5") (pinfunction "2Q_5") (pintype "tri_state"))
      (node (ref "U7") (pin "7") (pinfunction "INB_7") (pintype "input"))
    )
    (net (code "78") (name "Net-(U5A-3Q)") (class "Default")
      (node (ref "U5") (pin "6") (pinfunction "3Q_6") (pintype "tri_state"))
      (node (ref "U7") (pin "9") (pinfunction "INC_9") (pintype "input"))
    )
    (net (code "79") (name "Net-(U5A-4Q)") (class "Default")
      (node (ref "U5") (pin "9") (pinfunction "4Q_9") (pintype "tri_state"))
      (node (ref "U7") (pin "15") (pinfunction "IND_15") (pintype "input"))
    )
    (net (code "80") (name "Net-(U6-INA)") (class "Default")
      (node (ref "R11") (pin "1") (pinfunction "1_1") (pintype "passive"))
      (node (ref "U6") (pin "2") (pinfunction "INA_2") (pintype "bidirectional"))
      (node (ref "U7") (pin "2") (pinfunction "OUTA_2") (pintype "bidirectional"))
    )
    (net (code "81") (name "Net-(U6-INB)") (class "Default")
      (node (ref "R13") (pin "1") (pinfunction "1_1") (pintype "passive"))
      (node (ref "U6") (pin "6") (pinfunction "INB_6") (pintype "bidirectional"))
      (node (ref "U7") (pin "6") (pinfunction "OUTB_6") (pintype "bidirectional"))
    )
    (net (code "82") (name "Net-(U6-INC)") (class "Default")
      (node (ref "R14") (pin "1") (pinfunction "1_1") (pintype "passive"))
      (node (ref "U6") (pin "10") (pinfunction "INC_10") (pintype "bidirectional"))
      (node (ref "U7") (pin "10") (pinfunction "OUTC_10") (pintype "bidirectional"))
    )
    (net (code "83") (name "Net-(U6-IND)") (class "Default")
      (node (ref "R12") (pin "1") (pinfunction "1_1") (pintype "passive"))
      (node (ref "U6") (pin "14") (pinfunction "IND_14") (pintype "bidirectional"))
      (node (ref "U7") (pin "14") (pinfunction "OUTD_14") (pintype "bidirectional"))
    )
    (net (code "84") (name "Net-(U9A-D)") (class "Default")
      (node (ref "U9") (pin "2") (pinfunction "D_2") (pintype "input"))
      (node (ref "U9") (pin "6") (pinfunction "~{Q}_6") (pintype "output"))
    )
    (net (code "85") (name "Net-(U10-INA)") (class "Default")
      (node (ref "R15") (pin "1") (pinfunction "1_1") (pintype "passive"))
      (node (ref "U10") (pin "2") (pinfunction "INA_2") (pintype "bidirectional"))
      (node (ref "U11") (pin "2") (pinfunction "OUTA_2") (pintype "bidirectional"))
    )
    (net (code "86") (name "Net-(U10-INB)") (class "Default")
      (node (ref "R16") (pin "1") (pinfunction "1_1") (pintype "passive"))
      (node (ref "U10") (pin "6") (pinfunction "INB_6") (pintype "bidirectional"))
      (node (ref "U11") (pin "6") (pinfunction "OUTB_6") (pintype "bidirectional"))
    )
    (net (code "87") (name "Net-(U10-INC)") (class "Default")
      (node (ref "R17") (pin "1") (pinfunction "1_1") (pintype "passive"))
      (node (ref "U10") (pin "10") (pinfunction "INC_10") (pintype "bidirectional"))
      (node (ref "U11") (pin "10") (pinfunction "OUTC_10") (pintype "bidirectional"))
    )
    (net (code "88") (name "Net-(U10-IND)") (class "Default")
      (node (ref "R18") (pin "1") (pinfunction "1_1") (pintype "passive"))
      (node (ref "U10") (pin "14") (pinfunction "IND_14") (pintype "bidirectional"))
      (node (ref "U11") (pin "14") (pinfunction "OUTD_14") (pintype "bidirectional"))
    )
    (net (code "89") (name "Net-(U10-~{INA})") (class "Default")
      (node (ref "R82") (pin "1") (pinfunction "1_1") (pintype "passive"))
      (node (ref "R83") (pin "2") (pinfunction "2_2") (pintype "passive"))
      (node (ref "U10") (pin "1") (pinfunction "~{INA}_1") (pintype "bidirectional"))
      (node (ref "U10") (pin "15") (pinfunction "~{IND}_15") (pintype "bidirectional"))
      (node (ref "U10") (pin "7") (pinfunction "~{INB}_7") (pintype "bidirectional"))
      (node (ref "U10") (pin "9") (pinfunction "~{INC}_9") (pintype "bidirectional"))
      (node (ref "U25") (pin "1") (pinfunction "~{INA}_1") (pintype "bidirectional"))
      (node (ref "U25") (pin "15") (pinfunction "~{IND}_15") (pintype "bidirectional"))
      (node (ref "U25") (pin "7") (pinfunction "~{INB}_7") (pintype "bidirectional"))
      (node (ref "U25") (pin "9") (pinfunction "~{INC}_9") (pintype "bidirectional"))
      (node (ref "U6") (pin "1") (pinfunction "~{INA}_1") (pintype "bidirectional"))
      (node (ref "U6") (pin "15") (pinfunction "~{IND}_15") (pintype "bidirectional"))
      (node (ref "U6") (pin "7") (pinfunction "~{INB}_7") (pintype "bidirectional"))
      (node (ref "U6") (pin "9") (pinfunction "~{INC}_9") (pintype "bidirectional"))
    )
    (net (code "90") (name "Net-(U11-INA)") (class "Default")
      (node (ref "U11") (pin "1") (pinfunction "INA_1") (pintype "input"))
      (node (ref "U5") (pin "12") (pinfunction "5Q_12") (pintype "tri_state"))
    )
    (net (code "91") (name "Net-(U11-INB)") (class "Default")
      (node (ref "U11") (pin "7") (pinfunction "INB_7") (pintype "input"))
      (node (ref "U5") (pin "15") (pinfunction "6Q_15") (pintype "tri_state"))
    )
    (net (code "92") (name "Net-(U11-INC)") (class "Default")
      (node (ref "U11") (pin "9") (pinfunction "INC_9") (pintype "input"))
      (node (ref "U5") (pin "16") (pinfunction "7Q_16") (pintype "tri_state"))
    )
    (net (code "93") (name "Net-(U11-IND)") (class "Default")
      (node (ref "U11") (pin "15") (pinfunction "IND_15") (pintype "input"))
      (node (ref "U5") (pin "19") (pinfunction "8Q_19") (pintype "tri_state"))
    )
    (net (code "94") (name "Net-(U12-~{OE})") (class "Default")
      (node (ref "U12") (pin "24") (pinfunction "~{OE}_24") (pintype "passive"))
      (node (ref "U19") (pin "8") (pinfunction "O_8") (pintype "output"))
      (node (ref "U26") (pin "11") (pinfunction "I_11") (pintype "input"))
    )
    (net (code "95") (name "Net-(U13-~{OE})") (class "Default")
      (node (ref "U13") (pin "24") (pinfunction "~{OE}_24") (pintype "passive"))
      (node (ref "U26") (pin "10") (pinfunction "O_10") (pintype "output"))
    )
    (net (code "96") (name "Net-(U14-CLK)") (class "Default")
      (node (ref "U14") (pin "23") (pinfunction "CLK_23") (pintype "passive"))
      (node (ref "U28") (pin "2") (pinfunction "CLK_2") (pintype "passive"))
    )
    (net (code "97") (name "Net-(U14-OSC)") (class "Default")
      (node (ref "U14") (pin "24") (pinfunction "OSC_24") (pintype "passive"))
      (node (ref "W7") (pin "1") (pinfunction "1_1") (pintype "passive"))
    )
    (net (code "98") (name "Net-(U14-SH1)") (class "Default")
      (node (ref "U14") (pin "20") (pinfunction "SH1_20") (pintype "passive"))
      (node (ref "U28") (pin "6") (pinfunction "SAM1_6") (pintype "passive"))
    )
    (net (code "99") (name "Net-(U14-SH2)") (class "Default")
      (node (ref "U14") (pin "19") (pinfunction "SH2_19") (pintype "passive"))
      (node (ref "U28") (pin "5") (pinfunction "SAM2_5") (pintype "passive"))
    )
    (net (code "100") (name "Net-(U14-SO)") (class "Default")
      (node (ref "U14") (pin "21") (pinfunction "SO_21") (pintype "passive"))
      (node (ref "U28") (pin "4") (pinfunction "SO_4") (pintype "passive"))
    )
    (net (code "101") (name "Net-(U15-OUT1)") (class "Default")
      (node (ref "C63") (pin "+") (pinfunction "+_+") (pintype "passive"))
      (node (ref "R68") (pin "2") (pinfunction "2_2") (pintype "passive"))
      (node (ref "R69") (pin "1") (pinfunction "1_1") (pintype "passive"))
      (node (ref "U15") (pin "1") (pinfunction "OUT1_1") (pintype "passive"))
    )
    (net (code "102") (name "Net-(U15-VREF)") (class "Default")
      (node (ref "C98") (pin "1") (pinfunction "1_1") (pintype "passive"))
      (node (ref "U15") (pin "15") (pinfunction "VREF_15") (pintype "input"))
      (node (ref "U29") (pin "12") (pinfunction "+IN_12") (pintype "input"))
    )
    (net (code "103") (name "Net-(U16A-1Q)") (class "Default")
      (node (ref "R24") (pin "1") (pinfunction "1_1") (pintype "passive"))
      (node (ref "U16") (pin "2") (pinfunction "1Q_2") (pintype "tri_state"))
      (node (ref "U3") (pin "3") (pinfunction "A15_3") (pintype "passive"))
    )
    (net (code "104") (name "Net-(U16A-2Q)") (class "Default")
      (node (ref "R23") (pin "1") (pinfunction "1_1") (pintype "passive"))
      (node (ref "U16") (pin "5") (pinfunction "2Q_5") (pintype "tri_state"))
      (node (ref "U3") (pin "2") (pinfunction "A16_2") (pintype "passive"))
    )
    (net (code "105") (name "Net-(U16A-3Q)") (class "Default")
      (node (ref "R22") (pin "1") (pinfunction "1_1") (pintype "passive"))
      (node (ref "U16") (pin "6") (pinfunction "3Q_6") (pintype "tri_state"))
      (node (ref "W2") (pin "1") (pinfunction "1_1") (pintype "passive"))
    )
    (net (code "106") (name "Net-(U16A-4Q)") (class "Default")
      (node (ref "R26") (pin "1") (pinfunction "1_1") (pintype "passive"))
      (node (ref "U16") (pin "9") (pinfunction "4Q_9") (pintype "tri_state"))
      (node (ref "W3") (pin "1") (pinfunction "1_1") (pintype "passive"))
    )
    (net (code "107") (name "Net-(U16A-CLK)") (class "Default")
      (node (ref "U16") (pin "11") (pinfunction "CLK_11") (pintype "input"))
      (node (ref "U26") (pin "8") (pinfunction "O_8") (pintype "output"))
    )
    (net (code "108") (name "Net-(U16A-OC)") (class "Default")
      (node (ref "U16") (pin "1") (pinfunction "OC_1") (pintype "input"))
      (node (ref "U8") (pin "15") (pinfunction "Y0_15") (pintype "output"))
    )
    (net (code "109") (name "Net-(U18-7-IN)") (class "Default")
      (node (ref "P4") (pin "4") (pinfunction "4_4") (pintype "passive"))
      (node (ref "R91") (pin "1") (pinfunction "1_1") (pintype "passive"))
      (node (ref "U18") (pin "7") (pinfunction "7-IN_7") (pintype "passive"))
    )
    (net (code "110") (name "Net-(U18-11-IN)") (class "Default")
      (node (ref "U18") (pin "11") (pinfunction "11-IN_11") (pintype "passive"))
      (node (ref "U19") (pin "6") (pinfunction "O_6") (pintype "output"))
      (node (ref "U3") (pin "24") (pinfunction "~{OE}_24") (pintype "passive"))
    )
    (net (code "111") (name "Net-(U19A-I0)") (class "Default")
      (node (ref "U19") (pin "1") (pinfunction "I0_1") (pintype "input"))
      (node (ref "U21") (pin "2") (pinfunction "O_2") (pintype "output"))
    )
    (net (code "112") (name "Net-(U19B-I0)") (class "Default")
      (node (ref "U19") (pin "3") (pinfunction "I0_3") (pintype "input"))
      (node (ref "U20") (pin "5") (pinfunction "Y1_5") (pintype "output"))
    )
    (net (code "113") (name "Net-(U19B-I1)") (class "Default")
      (node (ref "U19") (pin "4") (pinfunction "I1_4") (pintype "input"))
      (node (ref "U20") (pin "6") (pinfunction "Y2_6") (pintype "output"))
    )
    (net (code "114") (name "Net-(U19B-I2)") (class "Default")
      (node (ref "U19") (pin "5") (pinfunction "I2_5") (pintype "input"))
      (node (ref "U20") (pin "7") (pinfunction "Y3_7") (pintype "output"))
      (node (ref "U26") (pin "9") (pinfunction "I_9") (pintype "input"))
    )
    (net (code "115") (name "Net-(U19C-I2)") (class "Default")
      (node (ref "U19") (pin "11") (pinfunction "I2_11") (pintype "input"))
      (node (ref "U26") (pin "12") (pinfunction "O_12") (pintype "output"))
    )
    (net (code "116") (name "Net-(U20A-Y0)") (class "Default")
      (node (ref "U20") (pin "15") (pinfunction "G_15") (pintype "input"))
      (node (ref "U20") (pin "4") (pinfunction "Y0_4") (pintype "output"))
    )
    (net (code "117") (name "Net-(U20B-Y1)") (class "Default")
      (node (ref "U20") (pin "11") (pinfunction "Y1_11") (pintype "output"))
      (node (ref "U8") (pin "4") (pinfunction "G2A_4") (pintype "input"))
      (node (ref "U8") (pin "5") (pinfunction "G2B_5") (pintype "input"))
    )
    (net (code "118") (name "Net-(U21C-O)") (class "Default")
      (node (ref "U21") (pin "1") (pinfunction "I_1") (pintype "input"))
      (node (ref "U21") (pin "8") (pinfunction "O_8") (pintype "output"))
    )
    (net (code "119") (name "Net-(U21F-I)") (class "Default")
      (node (ref "U21") (pin "5") (pinfunction "I_5") (pintype "input"))
      (node (ref "Y2") (pin "3") (pinfunction "OUT_3") (pintype "bidirectional"))
    )
    (net (code "120") (name "Net-(U21F-O)") (class "Default")
      (node (ref "U21") (pin "6") (pinfunction "O_6") (pintype "output"))
      (node (ref "U22") (pin "3") (pinfunction "CLK_3") (pintype "input"))
      (node (ref "U23") (pin "3") (pinfunction "CLK_3") (pintype "input"))
    )
    (net (code "121") (name "Net-(U22A-D)") (class "Default")
      (node (ref "U22") (pin "2") (pinfunction "D_2") (pintype "input"))
      (node (ref "U23") (pin "5") (pinfunction "Q_5") (pintype "output"))
      (node (ref "U4") (pin "35") (pinfunction "Q_35") (pintype "passive"))
    )
    (net (code "122") (name "Net-(U22A-PRE)") (class "Default")
      (node (ref "R10") (pin "1") (pinfunction "1_1") (pintype "passive"))
      (node (ref "U22") (pin "10") (pinfunction "PRE_10") (pintype "input"))
      (node (ref "U22") (pin "11") (pinfunction "CLK_11") (pintype "input"))
      (node (ref "U22") (pin "12") (pinfunction "D_12") (pintype "input"))
      (node (ref "U22") (pin "4") (pinfunction "PRE_4") (pintype "input"))
      (node (ref "U23") (pin "4") (pinfunction "PRE_4") (pintype "input"))
      (node (ref "U9") (pin "4") (pinfunction "PRE_4") (pintype "input"))
    )
    (net (code "123") (name "Net-(U22A-Q)") (class "Default")
      (node (ref "U22") (pin "5") (pinfunction "Q_5") (pintype "output"))
      (node (ref "U9") (pin "3") (pinfunction "CLK_3") (pintype "input"))
    )
    (net (code "124") (name "Net-(U23B-CLK)") (class "Default")
      (node (ref "U23") (pin "11") (pinfunction "CLK_11") (pintype "input"))
      (node (ref "U25") (pin "13") (pinfunction "OUTD_13") (pintype "bidirectional"))
    )
    (net (code "125") (name "Net-(U23B-D)") (class "Default")
      (node (ref "R4") (pin "1") (pinfunction "1_1") (pintype "passive"))
      (node (ref "U23") (pin "12") (pinfunction "D_12") (pintype "input"))
      (node (ref "U24") (pin "12") (pinfunction "~{EN}_12") (pintype "bidirectional"))
      (node (ref "U25") (pin "12") (pinfunction "~{EN}_12") (pintype "bidirectional"))
      (node (ref "U5") (pin "1") (pinfunction "OC_1") (pintype "input"))
    )
    (net (code "126") (name "Net-(U24-OUTA)") (class "Default")
      (node (ref "R21") (pin "1") (pinfunction "1_1") (pintype "passive"))
      (node (ref "U24") (pin "2") (pinfunction "OUTA_2") (pintype "bidirectional"))
    )
    (net (code "127") (name "Net-(U24-OUTB)") (class "Default")
      (node (ref "R20") (pin "1") (pinfunction "1_1") (pintype "passive"))
      (node (ref "U24") (pin "6") (pinfunction "OUTB_6") (pintype "bidirectional"))
    )
    (net (code "128") (name "Net-(U24-OUTD)") (class "Default")
      (node (ref "R19") (pin "1") (pinfunction "1_1") (pintype "passive"))
      (node (ref "U24") (pin "14") (pinfunction "OUTD_14") (pintype "bidirectional"))
    )
    (net (code "129") (name "Net-(U25-INC)") (class "Default")
      (node (ref "P1") (pin "16") (pinfunction "16_16") (pintype "passive"))
      (node (ref "R86") (pin "1") (pinfunction "1_1") (pintype "passive"))
      (node (ref "U25") (pin "10") (pinfunction "INC_10") (pintype "bidirectional"))
    )
    (net (code "130") (name "Net-(U26A-I)") (class "Default")
      (node (ref "C49") (pin "1") (pinfunction "1_1") (pintype "passive"))
      (node (ref "R32") (pin "1") (pinfunction "1_1") (pintype "passive"))
      (node (ref "U26") (pin "1") (pinfunction "I_1") (pintype "input"))
      (node (ref "Y1") (pin "1") (pinfunction "1_1") (pintype "passive"))
    )
    (net (code "131") (name "Net-(U26A-O)") (class "Default")
      (node (ref "R32") (pin "2") (pinfunction "2_2") (pintype "passive"))
      (node (ref "R34") (pin "1") (pinfunction "1_1") (pintype "passive"))
      (node (ref "U26") (pin "2") (pinfunction "O_2") (pintype "output"))
      (node (ref "U26") (pin "3") (pinfunction "I_3") (pintype "input"))
    )
    (net (code "132") (name "Net-(U26B-O)") (class "Default")
      (node (ref "C47") (pin "2") (pinfunction "2_2") (pintype "passive"))
      (node (ref "R34") (pin "2") (pinfunction "2_2") (pintype "passive"))
      (node (ref "U26") (pin "4") (pinfunction "O_4") (pintype "output"))
      (node (ref "U26") (pin "5") (pinfunction "I_5") (pintype "input"))
    )
    (net (code "133") (name "Net-(U26C-O)") (class "Default")
      (node (ref "U26") (pin "6") (pinfunction "O_6") (pintype "output"))
      (node (ref "W7") (pin "2") (pinfunction "2_2") (pintype "passive"))
    )
    (net (code "134") (name "Net-(U28-BIAS)") (class "Default")
      (node (ref "C55") (pin "2") (pinfunction "2_2") (pintype "passive"))
      (node (ref "R41") (pin "2") (pinfunction "2_2") (pintype "passive"))
      (node (ref "U28") (pin "13") (pinfunction "BIAS_13") (pintype "passive"))
      (node (ref "U29") (pin "7") (pinfunction "OUT_7") (pintype "output"))
    )
    (net (code "135") (name "Net-(U28-BIAS+)") (class "Default")
      (node (ref "C64") (pin "+") (pinfunction "+_+") (pintype "passive"))
      (node (ref "U28") (pin "15") (pinfunction "BIAS+_15") (pintype "passive"))
      (node (ref "U29") (pin "5") (pinfunction "+IN_5") (pintype "input"))
    )
    (net (code "136") (name "Net-(U28-BIAS-)") (class "Default")
      (node (ref "C55") (pin "1") (pinfunction "1_1") (pintype "passive"))
      (node (ref "U28") (pin "14") (pinfunction "BIAS-_14") (pintype "passive"))
      (node (ref "U29") (pin "6") (pinfunction "-IN_6") (pintype "input"))
    )
    (net (code "137") (name "Net-(U28-BUFF)") (class "Default")
      (node (ref "U28") (pin "12") (pinfunction "BUFF_12") (pintype "passive"))
      (node (ref "U29") (pin "3") (pinfunction "+IN_3") (pintype "input"))
    )
    (net (code "138") (name "Net-(U28-CH1)") (class "Default")
      (node (ref "C51") (pin "1") (pinfunction "1_1") (pintype "passive"))
      (node (ref "C53") (pin "-") (pinfunction "-_-") (pintype "passive"))
      (node (ref "R37") (pin "2") (pinfunction "2_2") (pintype "passive"))
      (node (ref "U28") (pin "9") (pinfunction "CH1_9") (pintype "passive"))
    )
    (net (code "139") (name "Net-(U28-CH2)") (class "Default")
      (node (ref "C56") (pin "1") (pinfunction "1_1") (pintype "passive"))
      (node (ref "C57") (pin "-") (pinfunction "-_-") (pintype "passive"))
      (node (ref "R42") (pin "2") (pinfunction "2_2") (pintype "passive"))
      (node (ref "U28") (pin "10") (pinfunction "CH2_10") (pintype "passive"))
    )
    (net (code "140") (name "Net-(U28-COM)") (class "Default")
      (node (ref "R43") (pin "2") (pinfunction "2_2") (pintype "passive"))
      (node (ref "U28") (pin "11") (pinfunction "COM_11") (pintype "passive"))
    )
    (net (code "141") (name "Net-(U29A--IN)") (class "Default")
      (node (ref "R43") (pin "1") (pinfunction "1_1") (pintype "passive"))
      (node (ref "U29") (pin "1") (pinfunction "OUT_1") (pintype "output"))
      (node (ref "U29") (pin "2") (pinfunction "-IN_2") (pintype "input"))
    )
    (net (code "142") (name "Net-(U29C-+IN)") (class "Default")
      (node (ref "C1") (pin "+") (pinfunction "+_+") (pintype "passive"))
      (node (ref "R55") (pin "1") (pinfunction "1_1") (pintype "passive"))
      (node (ref "R60") (pin "2") (pinfunction "2_2") (pintype "passive"))
      (node (ref "U29") (pin "10") (pinfunction "+IN_10") (pintype "input"))
    )
    (net (code "143") (name "Net-(U29D--IN)") (class "Default")
      (node (ref "C1") (pin "-") (pinfunction "-_-") (pintype "passive"))
      (node (ref "R59") (pin "2") (pinfunction "2_2") (pintype "passive"))
      (node (ref "U29") (pin "13") (pinfunction "-IN_13") (pintype "input"))
      (node (ref "U29") (pin "14") (pinfunction "OUT_14") (pintype "output"))
    )
    (net (code "144") (name "Net-(U30-CNTL)") (class "Default")
      (node (ref "C66") (pin "+") (pinfunction "+_+") (pintype "passive"))
      (node (ref "C97") (pin "2") (pinfunction "2_2") (pintype "passive"))
      (node (ref "R87") (pin "1") (pinfunction "1_1") (pintype "passive"))
      (node (ref "U30") (pin "2") (pinfunction "CNTL_2") (pintype "passive"))
    )
    (net (code "145") (name "Net-(U30-ROLOFF)") (class "Default")
      (node (ref "C76") (pin "1") (pinfunction "1_1") (pintype "passive"))
      (node (ref "U30") (pin "5") (pinfunction "ROLOFF_5") (pintype "passive"))
    )
    (net (code "146") (name "Net-(U30-VO)") (class "Default")
      (node (ref "R71") (pin "1") (pinfunction "1_1") (pintype "passive"))
      (node (ref "R80") (pin "2") (pinfunction "2_2") (pintype "passive"))
      (node (ref "U30") (pin "7") (pinfunction "VO_7") (pintype "output"))
    )
    (net (code "147") (name "Net-(U31-AMP1)") (class "Default")
      (node (ref "C78") (pin "1") (pinfunction "1_1") (pintype "passive"))
      (node (ref "C81") (pin "-") (pinfunction "-_-") (pintype "passive"))
      (node (ref "R31") (pin "1") (pinfunction "1_1") (pintype "passive"))
      (node (ref "U31") (pin "3") (pinfunction "AMP1_3") (pintype "passive"))
    )
    (net (code "148") (name "Net-(U31-FDBK1)") (class "Default")
      (node (ref "C87") (pin "+") (pinfunction "+_+") (pintype "passive"))
      (node (ref "U31") (pin "14") (pinfunction "FDBK1_14") (pintype "passive"))
    )
    (net (code "149") (name "Net-(U31-FDBK2)") (class "Default")
      (node (ref "C86") (pin "+") (pinfunction "+_+") (pintype "passive"))
      (node (ref "U31") (pin "10") (pinfunction "FDBK2_10") (pintype "passive"))
    )
    (net (code "150") (name "Net-(U31-OUT1)") (class "Default")
      (node (ref "C87") (pin "-") (pinfunction "-_-") (pintype "passive"))
      (node (ref "C91") (pin "1") (pinfunction "1_1") (pintype "passive"))
      (node (ref "C92") (pin "1") (pinfunction "1_1") (pintype "passive"))
      (node (ref "P7") (pin "1") (pinfunction "1_1") (pintype "passive"))
      (node (ref "P7") (pin "2") (pinfunction "2_2") (pintype "passive"))
      (node (ref "U31") (pin "15") (pinfunction "OUT1_15") (pintype "output"))
    )
    (net (code "151") (name "Net-(U31-OUT2)") (class "Default")
      (node (ref "C86") (pin "-") (pinfunction "-_-") (pintype "passive"))
      (node (ref "C90") (pin "2") (pinfunction "2_2") (pintype "passive"))
      (node (ref "P7") (pin "3") (pinfunction "3_3") (pintype "passive"))
      (node (ref "P7") (pin "4") (pinfunction "4_4") (pintype "passive"))
      (node (ref "R73") (pin "2") (pinfunction "2_2") (pintype "passive"))
      (node (ref "U31") (pin "8") (pinfunction "OUT2_8") (pintype "output"))
    )
    (net (code "152") (name "Net-(U31-PROT)") (class "Default")
      (node (ref "C80") (pin "+") (pinfunction "+_+") (pintype "passive"))
      (node (ref "U31") (pin "5") (pinfunction "PROT_5") (pintype "passive"))
    )
    (net (code "153") (name "Net-(U31-PROT_FLT)") (class "Default")
      (node (ref "C84") (pin "+") (pinfunction "+_+") (pintype "passive"))
      (node (ref "U31") (pin "2") (pinfunction "PROT_FLT_2") (pintype "passive"))
    )
    (net (code "154") (name "Net-(U31-~{AMP1})") (class "Default")
      (node (ref "C79") (pin "+") (pinfunction "+_+") (pintype "passive"))
      (node (ref "U31") (pin "1") (pinfunction "~{AMP1}_1") (pintype "passive"))
    )
    (net (code "155") (name "Net-(U31-~{AMP2})") (class "Default")
      (node (ref "C83") (pin "+") (pinfunction "+_+") (pintype "passive"))
      (node (ref "U31") (pin "6") (pinfunction "~{AMP2}_6") (pintype "passive"))
    )
    (net (code "156") (name "Net-(U32A-+IN)") (class "Default")
      (node (ref "C46") (pin "+") (pinfunction "+_+") (pintype "passive"))
      (node (ref "R33") (pin "2") (pinfunction "2_2") (pintype "passive"))
      (node (ref "R48") (pin "1") (pinfunction "1_1") (pintype "passive"))
      (node (ref "U32") (pin "3") (pinfunction "+IN_3") (pintype "input"))
    )
    (net (code "157") (name "Net-(U32A--IN)") (class "Default")
      (node (ref "R39") (pin "2") (pinfunction "2_2") (pintype "passive"))
      (node (ref "U32") (pin "1") (pinfunction "OUT_1") (pintype "output"))
      (node (ref "U32") (pin "2") (pinfunction "-IN_2") (pintype "input"))
    )
    (net (code "158") (name "Net-(U32B-+IN)") (class "Default")
      (node (ref "C48") (pin "1") (pinfunction "1_1") (pintype "passive"))
      (node (ref "R36") (pin "1") (pinfunction "1_1") (pintype "passive"))
      (node (ref "U32") (pin "5") (pinfunction "+IN_5") (pintype "input"))
    )
    (net (code "159") (name "Net-(U32C-+IN)") (class "Default")
      (node (ref "C73") (pin "+") (pinfunction "+_+") (pintype "passive"))
      (node (ref "R54") (pin "2") (pinfunction "2_2") (pintype "passive"))
      (node (ref "R65") (pin "1") (pinfunction "1_1") (pintype "passive"))
      (node (ref "U32") (pin "10") (pinfunction "+IN_10") (pintype "input"))
      (node (ref "U33") (pin "10") (pinfunction "+IN_10") (pintype "input"))
      (node (ref "U33") (pin "12") (pinfunction "+IN_12") (pintype "input"))
      (node (ref "U33") (pin "3") (pinfunction "+IN_3") (pintype "input"))
      (node (ref "U33") (pin "5") (pinfunction "+IN_5") (pintype "input"))
    )
    (net (code "160") (name "Net-(U32C--IN)") (class "Default")
      (node (ref "C59") (pin "2") (pinfunction "2_2") (pintype "passive"))
      (node (ref "R46") (pin "1") (pinfunction "1_1") (pintype "passive"))
      (node (ref "U32") (pin "9") (pinfunction "-IN_9") (pintype "input"))
    )
    (net (code "161") (name "Net-(U32C-OUT)") (class "Default")
      (node (ref "C59") (pin "1") (pinfunction "1_1") (pintype "passive"))
      (node (ref "R45") (pin "1") (pinfunction "1_1") (pintype "passive"))
      (node (ref "R78") (pin "2") (pinfunction "2_2") (pintype "passive"))
      (node (ref "U32") (pin "8") (pinfunction "OUT_8") (pintype "output"))
    )
    (net (code "162") (name "Net-(U32D-+IN)") (class "Default")
      (node (ref "C50") (pin "1") (pinfunction "1_1") (pintype "passive"))
      (node (ref "R38") (pin "1") (pinfunction "1_1") (pintype "passive"))
      (node (ref "U32") (pin "12") (pinfunction "+IN_12") (pintype "input"))
    )
    (net (code "163") (name "Net-(U32D--IN)") (class "Default")
      (node (ref "C52") (pin "1") (pinfunction "1_1") (pintype "passive"))
      (node (ref "R35") (pin "2") (pinfunction "2_2") (pintype "passive"))
      (node (ref "U32") (pin "13") (pinfunction "-IN_13") (pintype "input"))
      (node (ref "U32") (pin "14") (pinfunction "OUT_14") (pintype "output"))
    )
    (net (code "164") (name "Net-(U33A--IN)") (class "Default")
      (node (ref "C71") (pin "2") (pinfunction "2_2") (pintype "passive"))
      (node (ref "R64") (pin "1") (pinfunction "1_1") (pintype "passive"))
      (node (ref "U33") (pin "2") (pinfunction "-IN_2") (pintype "input"))
    )
    (net (code "165") (name "Net-(U33A-OUT)") (class "Default")
      (node (ref "C71") (pin "1") (pinfunction "1_1") (pintype "passive"))
      (node (ref "R63") (pin "1") (pinfunction "1_1") (pintype "passive"))
      (node (ref "R79") (pin "2") (pinfunction "2_2") (pintype "passive"))
      (node (ref "U33") (pin "1") (pinfunction "OUT_1") (pintype "output"))
    )
    (net (code "166") (name "Net-(U33B--IN)") (class "Default")
      (node (ref "C60") (pin "2") (pinfunction "2_2") (pintype "passive"))
      (node (ref "R52") (pin "1") (pinfunction "1_1") (pintype "passive"))
      (node (ref "U33") (pin "6") (pinfunction "-IN_6") (pintype "input"))
    )
    (net (code "167") (name "Net-(U33B-OUT)") (class "Default")
      (node (ref "C60") (pin "1") (pinfunction "1_1") (pintype "passive"))
      (node (ref "R51") (pin "1") (pinfunction "1_1") (pintype "passive"))
      (node (ref "R77") (pin "2") (pinfunction "2_2") (pintype "passive"))
      (node (ref "U33") (pin "7") (pinfunction "OUT_7") (pintype "output"))
    )
    (net (code "168") (name "Net-(U33C--IN)") (class "Default")
      (node (ref "R67") (pin "2") (pinfunction "2_2") (pintype "passive"))
      (node (ref "R80") (pin "1") (pinfunction "1_1") (pintype "passive"))
      (node (ref "U33") (pin "9") (pinfunction "-IN_9") (pintype "input"))
    )
    (net (code "169") (name "Net-(U33C-OUT)") (class "Default")
      (node (ref "C75") (pin "+") (pinfunction "+_+") (pintype "passive"))
      (node (ref "R67") (pin "1") (pinfunction "1_1") (pintype "passive"))
      (node (ref "U33") (pin "8") (pinfunction "OUT_8") (pintype "output"))
    )
    (net (code "170") (name "Net-(U33D--IN)") (class "Default")
      (node (ref "C96") (pin "1") (pinfunction "1_1") (pintype "passive"))
      (node (ref "R53") (pin "1") (pinfunction "1_1") (pintype "passive"))
      (node (ref "R77") (pin "1") (pinfunction "1_1") (pintype "passive"))
      (node (ref "R78") (pin "1") (pinfunction "1_1") (pintype "passive"))
      (node (ref "R79") (pin "1") (pinfunction "1_1") (pintype "passive"))
      (node (ref "R81") (pin "1") (pinfunction "1_1") (pintype "passive"))
      (node (ref "R88") (pin "2") (pinfunction "2_2") (pintype "passive"))
      (node (ref "U33") (pin "13") (pinfunction "-IN_13") (pintype "input"))
    )
    (net (code "171") (name "Net-(U33D-OUT)") (class "Default")
      (node (ref "C68") (pin "+") (pinfunction "+_+") (pintype "passive"))
      (node (ref "C96") (pin "2") (pinfunction "2_2") (pintype "passive"))
      (node (ref "R88") (pin "1") (pinfunction "1_1") (pintype "passive"))
      (node (ref "U33") (pin "14") (pinfunction "OUT_14") (pintype "output"))
    )
    (net (code "172") (name "PCM-A0") (class "Default")
      (node (ref "U1") (pin "18") (pinfunction "A0_18") (pintype "passive"))
      (node (ref "U12") (pin "12") (pinfunction "A0_12") (pintype "passive"))
      (node (ref "U13") (pin "12") (pinfunction "A0_12") (pintype "passive"))
    )
    (net (code "173") (name "PCM-A1") (class "Default")
      (node (ref "U1") (pin "19") (pinfunction "A1_19") (pintype "passive"))
      (node (ref "U12") (pin "11") (pinfunction "A1_11") (pintype "passive"))
      (node (ref "U13") (pin "11") (pinfunction "A1_11") (pintype "passive"))
    )
    (net (code "174") (name "PCM-A2") (class "Default")
      (node (ref "U1") (pin "20") (pinfunction "A2_20") (pintype "passive"))
      (node (ref "U12") (pin "10") (pinfunction "A2_10") (pintype "passive"))
      (node (ref "U13") (pin "10") (pinfunction "A2_10") (pintype "passive"))
    )
    (net (code "175") (name "PCM-A3") (class "Default")
      (node (ref "U1") (pin "21") (pinfunction "A3_21") (pintype "passive"))
      (node (ref "U12") (pin "9") (pinfunction "A3_9") (pintype "passive"))
      (node (ref "U13") (pin "9") (pinfunction "A3_9") (pintype "passive"))
    )
    (net (code "176") (name "PCM-A4") (class "Default")
      (node (ref "U1") (pin "22") (pinfunction "A4_22") (pintype "passive"))
      (node (ref "U12") (pin "8") (pinfunction "A4_8") (pintype "passive"))
      (node (ref "U13") (pin "8") (pinfunction "A4_8") (pintype "passive"))
    )
    (net (code "177") (name "PCM-A5") (class "Default")
      (node (ref "U1") (pin "23") (pinfunction "A5_23") (pintype "passive"))
      (node (ref "U12") (pin "7") (pinfunction "A5_7") (pintype "passive"))
      (node (ref "U13") (pin "7") (pinfunction "A5_7") (pintype "passive"))
    )
    (net (code "178") (name "PCM-A6") (class "Default")
      (node (ref "U1") (pin "24") (pinfunction "A6_24") (pintype "passive"))
      (node (ref "U12") (pin "6") (pinfunction "A6_6") (pintype "passive"))
      (node (ref "U13") (pin "6") (pinfunction "A6_6") (pintype "passive"))
    )
    (net (code "179") (name "PCM-A7") (class "Default")
      (node (ref "U1") (pin "25") (pinfunction "A7_25") (pintype "passive"))
      (node (ref "U12") (pin "5") (pinfunction "A7_5") (pintype "passive"))
      (node (ref "U13") (pin "5") (pinfunction "A7_5") (pintype "passive"))
    )
    (net (code "180") (name "PCM-A8") (class "Default")
      (node (ref "U1") (pin "26") (pinfunction "A8_26") (pintype "passive"))
      (node (ref "U12") (pin "27") (pinfunction "A8_27") (pintype "passive"))
      (node (ref "U13") (pin "27") (pinfunction "A8_27") (pintype "passive"))
    )
    (net (code "181") (name "PCM-A9") (class "Default")
      (node (ref "U1") (pin "27") (pinfunction "A9_27") (pintype "passive"))
      (node (ref "U12") (pin "26") (pinfunction "A9_26") (pintype "passive"))
      (node (ref "U13") (pin "26") (pinfunction "A9_26") (pintype "passive"))
    )
    (net (code "182") (name "PCM-A10") (class "Default")
      (node (ref "U1") (pin "28") (pinfunction "A10_28") (pintype "passive"))
      (node (ref "U12") (pin "23") (pinfunction "A10_23") (pintype "passive"))
      (node (ref "U13") (pin "23") (pinfunction "A10_23") (pintype "passive"))
    )
    (net (code "183") (name "PCM-A11") (class "Default")
      (node (ref "U1") (pin "29") (pinfunction "A11_29") (pintype "passive"))
      (node (ref "U12") (pin "25") (pinfunction "A11_25") (pintype "passive"))
      (node (ref "U13") (pin "25") (pinfunction "A11_25") (pintype "passive"))
    )
    (net (code "184") (name "PCM-A12") (class "Default")
      (node (ref "U1") (pin "30") (pinfunction "A12_30") (pintype "passive"))
      (node (ref "U12") (pin "4") (pinfunction "A12_4") (pintype "passive"))
      (node (ref "U13") (pin "4") (pinfunction "A12_4") (pintype "passive"))
    )
    (net (code "185") (name "PCM-A13") (class "Default")
      (node (ref "U1") (pin "31") (pinfunction "A13_31") (pintype "passive"))
      (node (ref "U12") (pin "28") (pinfunction "A13_28") (pintype "passive"))
      (node (ref "U13") (pin "28") (pinfunction "A13_28") (pintype "passive"))
    )
    (net (code "186") (name "PCM-A14") (class "Default")
      (node (ref "U1") (pin "32") (pinfunction "A14_32") (pintype "passive"))
      (node (ref "U12") (pin "29") (pinfunction "A14_29") (pintype "passive"))
      (node (ref "U13") (pin "29") (pinfunction "A14_29") (pintype "passive"))
    )
    (net (code "187") (name "PCM-A15") (class "Default")
      (node (ref "U1") (pin "33") (pinfunction "A15_33") (pintype "passive"))
      (node (ref "U12") (pin "3") (pinfunction "A15_3") (pintype "passive"))
      (node (ref "U13") (pin "3") (pinfunction "A15_3") (pintype "passive"))
    )
    (net (code "188") (name "PCM-A16") (class "Default")
      (node (ref "U1") (pin "34") (pinfunction "A16_34") (pintype "passive"))
      (node (ref "U12") (pin "2") (pinfunction "A16_2") (pintype "passive"))
      (node (ref "U13") (pin "2") (pinfunction "A16_2") (pintype "passive"))
    )
    (net (code "189") (name "PCM-A17") (class "Default")
      (node (ref "U1") (pin "35") (pinfunction "A17_35") (pintype "passive"))
      (node (ref "U18") (pin "4") (pinfunction "4-IN_4") (pintype "passive"))
      (node (ref "U26") (pin "13") (pinfunction "I_13") (pintype "input"))
    )
    (net (code "190") (name "PCM-BS") (class "Default")
      (node (ref "U17") (pin "9") (pinfunction "CLK_9") (pintype "input"))
      (node (ref "U8") (pin "10") (pinfunction "Y5_10") (pintype "output"))
    )
    (net (code "191") (name "PCM-D0") (class "Default")
      (node (ref "U1") (pin "9") (pinfunction "SD0_9") (pintype "passive"))
      (node (ref "U12") (pin "13") (pinfunction "D0_13") (pintype "passive"))
      (node (ref "U13") (pin "13") (pinfunction "D0_13") (pintype "passive"))
    )
    (net (code "192") (name "PCM-D1") (class "Default")
      (node (ref "U1") (pin "10") (pinfunction "SD1_10") (pintype "passive"))
      (node (ref "U12") (pin "14") (pinfunction "D1_14") (pintype "passive"))
      (node (ref "U13") (pin "14") (pinfunction "D1_14") (pintype "passive"))
    )
    (net (code "193") (name "PCM-D2") (class "Default")
      (node (ref "U1") (pin "11") (pinfunction "SD2_11") (pintype "passive"))
      (node (ref "U12") (pin "15") (pinfunction "D2_15") (pintype "passive"))
      (node (ref "U13") (pin "15") (pinfunction "D2_15") (pintype "passive"))
    )
    (net (code "194") (name "PCM-D3") (class "Default")
      (node (ref "U1") (pin "12") (pinfunction "SD3_12") (pintype "passive"))
      (node (ref "U12") (pin "17") (pinfunction "D3_17") (pintype "passive"))
      (node (ref "U13") (pin "17") (pinfunction "D3_17") (pintype "passive"))
      (node (ref "U13") (pin "18") (pinfunction "D4_18") (pintype "passive"))
    )
    (net (code "195") (name "PCM-D4") (class "Default")
      (node (ref "U1") (pin "13") (pinfunction "SD4_13") (pintype "passive"))
      (node (ref "U12") (pin "18") (pinfunction "D4_18") (pintype "passive"))
    )
    (net (code "196") (name "PCM-D5") (class "Default")
      (node (ref "U1") (pin "14") (pinfunction "SD5_14") (pintype "passive"))
      (node (ref "U12") (pin "19") (pinfunction "D5_19") (pintype "passive"))
      (node (ref "U13") (pin "19") (pinfunction "D5_19") (pintype "passive"))
    )
    (net (code "197") (name "PCM-D6") (class "Default")
      (node (ref "U1") (pin "15") (pinfunction "SD6_15") (pintype "passive"))
      (node (ref "U12") (pin "20") (pinfunction "D6_20") (pintype "passive"))
      (node (ref "U13") (pin "20") (pinfunction "D6_20") (pintype "passive"))
    )
    (net (code "198") (name "PCM-D7") (class "Default")
      (node (ref "U1") (pin "16") (pinfunction "SD7_16") (pintype "passive"))
      (node (ref "U12") (pin "21") (pinfunction "D7_21") (pintype "passive"))
      (node (ref "U13") (pin "21") (pinfunction "D7_21") (pintype "passive"))
    )
    (net (code "199") (name "PCM-OUT") (class "Default")
      (node (ref "C58") (pin "1") (pinfunction "1_1") (pintype "passive"))
      (node (ref "R81") (pin "2") (pinfunction "2_2") (pintype "passive"))
      (node (ref "U32") (pin "6") (pinfunction "-IN_6") (pintype "input"))
      (node (ref "U32") (pin "7") (pinfunction "OUT_7") (pintype "output"))
    )
    (net (code "200") (name "RA17-0") (class "Default")
      (node (ref "U12") (pin "30") (pinfunction "A17_30") (pintype "passive"))
      (node (ref "U18") (pin "17") (pinfunction "I/O-17_17") (pintype "passive"))
    )
    (net (code "201") (name "RA17-1") (class "Default")
      (node (ref "U13") (pin "30") (pinfunction "A17_30") (pintype "passive"))
      (node (ref "U18") (pin "14") (pinfunction "I/O-14_14") (pintype "passive"))
    )
    (net (code "202") (name "RA18-0") (class "Default")
      (node (ref "U12") (pin "31") (pinfunction "A18_31") (pintype "passive"))
      (node (ref "U18") (pin "12") (pinfunction "OUT-12_12") (pintype "passive"))
    )
    (net (code "203") (name "RA18-1") (class "Default")
      (node (ref "U13") (pin "31") (pinfunction "A18_31") (pintype "passive"))
      (node (ref "U18") (pin "13") (pinfunction "I/O-13_13") (pintype "passive"))
    )
    (net (code "204") (name "RD-LATCH") (class "Default")
      (node (ref "U10") (pin "12") (pinfunction "~{EN}_12") (pintype "bidirectional"))
      (node (ref "U23") (pin "10") (pinfunction "PRE_10") (pintype "input"))
      (node (ref "U24") (pin "7") (pinfunction "INB_7") (pintype "input"))
      (node (ref "U6") (pin "12") (pinfunction "~{EN}_12") (pintype "bidirectional"))
      (node (ref "U8") (pin "11") (pinfunction "Y4_11") (pintype "output"))
    )
    (net (code "205") (name "RESET") (class "Default")
      (node (ref "R3") (pin "1") (pinfunction "1_1") (pintype "passive"))
      (node (ref "U1") (pin "8") (pinfunction "~{RESET}_8") (pintype "passive"))
      (node (ref "U14") (pin "3") (pinfunction "~{RESET}_3") (pintype "passive"))
      (node (ref "U19") (pin "12") (pinfunction "O_12") (pintype "output"))
      (node (ref "U28") (pin "7") (pinfunction "~{RESET}_7") (pintype "passive"))
      (node (ref "U4") (pin "37") (pinfunction "~{RESET}_37") (pintype "passive"))
    )
    (net (code "206") (name "R{slash}W") (class "Default")
      (node (ref "U18") (pin "9") (pinfunction "9-IN_9") (pintype "passive"))
      (node (ref "U4") (pin "32") (pinfunction "R/W_32") (pintype "passive"))
    )
    (net (code "207") (name "SND_DAT0") (class "Default")
      (node (ref "C35") (pin "1") (pinfunction "1_1") (pintype "passive"))
      (node (ref "P1") (pin "3") (pinfunction "3_3") (pintype "passive"))
      (node (ref "R11") (pin "2") (pinfunction "2_2") (pintype "passive"))
    )
    (net (code "208") (name "SND_DAT1") (class "Default")
      (node (ref "C37") (pin "1") (pinfunction "1_1") (pintype "passive"))
      (node (ref "P1") (pin "4") (pinfunction "4_4") (pintype "passive"))
      (node (ref "R13") (pin "2") (pinfunction "2_2") (pintype "passive"))
    )
    (net (code "209") (name "SND_DAT2") (class "Default")
      (node (ref "C38") (pin "1") (pinfunction "1_1") (pintype "passive"))
      (node (ref "P1") (pin "5") (pinfunction "5_5") (pintype "passive"))
      (node (ref "R14") (pin "2") (pinfunction "2_2") (pintype "passive"))
    )
    (net (code "210") (name "SND_DAT3") (class "Default")
      (node (ref "C36") (pin "1") (pinfunction "1_1") (pintype "passive"))
      (node (ref "P1") (pin "6") (pinfunction "6_6") (pintype "passive"))
      (node (ref "R12") (pin "2") (pinfunction "2_2") (pintype "passive"))
    )
    (net (code "211") (name "SND_DAT4") (class "Default")
      (node (ref "C39") (pin "1") (pinfunction "1_1") (pintype "passive"))
      (node (ref "P1") (pin "7") (pinfunction "7_7") (pintype "passive"))
      (node (ref "R15") (pin "2") (pinfunction "2_2") (pintype "passive"))
    )
    (net (code "212") (name "SND_DAT5") (class "Default")
      (node (ref "C40") (pin "1") (pinfunction "1_1") (pintype "passive"))
      (node (ref "P1") (pin "8") (pinfunction "8_8") (pintype "passive"))
      (node (ref "R16") (pin "2") (pinfunction "2_2") (pintype "passive"))
    )
    (net (code "213") (name "SND_DAT6") (class "Default")
      (node (ref "C41") (pin "1") (pinfunction "1_1") (pintype "passive"))
      (node (ref "P1") (pin "9") (pinfunction "9_9") (pintype "passive"))
      (node (ref "R17") (pin "2") (pinfunction "2_2") (pintype "passive"))
    )
    (net (code "214") (name "SND_DAT7") (class "Default")
      (node (ref "C42") (pin "1") (pinfunction "1_1") (pintype "passive"))
      (node (ref "P1") (pin "10") (pinfunction "10_10") (pintype "passive"))
      (node (ref "R18") (pin "2") (pinfunction "2_2") (pintype "passive"))
    )
    (net (code "215") (name "SND_DAT8") (class "Default")
      (node (ref "P1") (pin "18") (pinfunction "18_18") (pintype "passive"))
      (node (ref "R84") (pin "1") (pinfunction "1_1") (pintype "passive"))
      (node (ref "U25") (pin "2") (pinfunction "INA_2") (pintype "bidirectional"))
    )
    (net (code "216") (name "SND_DAV") (class "Default")
      (node (ref "C45") (pin "1") (pinfunction "1_1") (pintype "passive"))
      (node (ref "P1") (pin "19") (pinfunction "19_19") (pintype "passive"))
      (node (ref "R21") (pin "2") (pinfunction "2_2") (pintype "passive"))
    )
    (net (code "217") (name "SND_RDY") (class "Default")
      (node (ref "C43") (pin "1") (pinfunction "1_1") (pintype "passive"))
      (node (ref "P1") (pin "11") (pinfunction "11_11") (pintype "passive"))
      (node (ref "R19") (pin "2") (pinfunction "2_2") (pintype "passive"))
    )
    (net (code "218") (name "SOFT_RES") (class "Default")
      (node (ref "U19") (pin "13") (pinfunction "I2_13") (pintype "input"))
      (node (ref "U25") (pin "3") (pinfunction "OUTA_3") (pintype "bidirectional"))
    )
    (net (code "219") (name "VIDPWRON") (class "Default")
      (node (ref "U19") (pin "2") (pinfunction "I1_2") (pintype "input"))
      (node (ref "U25") (pin "5") (pinfunction "OUTB_5") (pintype "bidirectional"))
    )
    (net (code "220") (name "VIDSNDRD") (class "Default")
      (node (ref "U11") (pin "12") (pinfunction "~{EN}_12") (pintype "bidirectional"))
      (node (ref "U25") (pin "11") (pinfunction "OUTC_11") (pintype "bidirectional"))
      (node (ref "U7") (pin "12") (pinfunction "~{EN}_12") (pintype "bidirectional"))
      (node (ref "U9") (pin "13") (pinfunction "CLR_13") (pintype "input"))
    )
    (net (code "221") (name "WR-LATCH") (class "Default")
      (node (ref "U5") (pin "11") (pinfunction "CLK_11") (pintype "input"))
      (node (ref "U8") (pin "7") (pinfunction "Y7_7") (pintype "output"))
      (node (ref "U9") (pin "11") (pinfunction "CLK_11") (pintype "input"))
    )
    (net (code "222") (name "YAM") (class "Default")
      (node (ref "U14") (pin "7") (pinfunction "~{CS}_7") (pintype "passive"))
      (node (ref "U8") (pin "14") (pinfunction "Y1_14") (pintype "output"))
    )
    (net (code "223") (name "YAM1-OUT") (class "Default")
      (node (ref "C53") (pin "+") (pinfunction "+_+") (pintype "passive"))
      (node (ref "R40") (pin "2") (pinfunction "2_2") (pintype "passive"))
    )
    (net (code "224") (name "YAM2-OUT") (class "Default")
      (node (ref "C57") (pin "+") (pinfunction "+_+") (pintype "passive"))
      (node (ref "R44") (pin "2") (pinfunction "2_2") (pintype "passive"))
    )
    (net (code "225") (name "unconnected-(P1-Pad2)") (class "Default")
      (node (ref "P1") (pin "2") (pinfunction "2_2") (pintype "passive"))
    )
    (net (code "226") (name "unconnected-(P1-Pad12)") (class "Default")
      (node (ref "P1") (pin "12") (pinfunction "12_12") (pintype "passive"))
    )
    (net (code "227") (name "unconnected-(P1-Pad14)") (class "Default")
      (node (ref "P1") (pin "14") (pinfunction "14_14") (pintype "passive"))
    )
    (net (code "228") (name "unconnected-(P1-Pad20)") (class "Default")
      (node (ref "P1") (pin "20") (pinfunction "20_20") (pintype "passive"))
    )
    (net (code "229") (name "unconnected-(P2-Pad2)") (class "Default")
      (node (ref "P2") (pin "2") (pinfunction "2_2") (pintype "passive"))
    )
    (net (code "230") (name "unconnected-(P3-Pad2)") (class "Default")
      (node (ref "P3") (pin "2") (pinfunction "2_2") (pintype "passive"))
    )
    (net (code "231") (name "unconnected-(P4-Pad2)") (class "Default")
      (node (ref "P4") (pin "2") (pinfunction "2_2") (pintype "passive"))
    )
    (net (code "232") (name "unconnected-(P4-Pad3)") (class "Default")
      (node (ref "P4") (pin "3") (pinfunction "3_3") (pintype "passive"))
    )
    (net (code "233") (name "unconnected-(P5-Pad1)") (class "Default")
      (node (ref "P5") (pin "1") (pinfunction "1_1") (pintype "passive"))
    )
    (net (code "234") (name "unconnected-(P5-Pad3)") (class "Default")
      (node (ref "P5") (pin "3") (pinfunction "3_3") (pintype "passive"))
    )
    (net (code "235") (name "unconnected-(P6-Pad3)") (class "Default")
      (node (ref "P6") (pin "3") (pinfunction "3_3") (pintype "passive"))
    )
    (net (code "236") (name "unconnected-(P6-Pad4)") (class "Default")
      (node (ref "P6") (pin "4") (pinfunction "4_4") (pintype "passive"))
    )
    (net (code "237") (name "unconnected-(U1-~{XTAL}-Pad6)") (class "Default")
      (node (ref "U1") (pin "6") (pinfunction "~{XTAL}_6") (pintype "passive"))
    )
    (net (code "238") (name "unconnected-(U4-AVMA-Pad36)") (class "Default")
      (node (ref "U4") (pin "36") (pinfunction "AVMA_36") (pintype "passive"))
    )
    (net (code "239") (name "unconnected-(U4-BA-Pad6)") (class "Default")
      (node (ref "U4") (pin "6") (pinfunction "BA_6") (pintype "passive"))
    )
    (net (code "240") (name "unconnected-(U4-BS-Pad5)") (class "Default")
      (node (ref "U4") (pin "5") (pinfunction "BS_5") (pintype "passive"))
    )
    (net (code "241") (name "unconnected-(U4-BUSY-Pad33)") (class "Default")
      (node (ref "U4") (pin "33") (pinfunction "BUSY_33") (pintype "passive"))
    )
    (net (code "242") (name "unconnected-(U4-LIC-Pad38)") (class "Default")
      (node (ref "U4") (pin "38") (pinfunction "LIC_38") (pintype "passive"))
    )
    (net (code "243") (name "unconnected-(U4-VCC-Pad7)") (class "Default")
      (node (ref "U4") (pin "7") (pinfunction "VCC_7") (pintype "passive"))
    )
    (net (code "244") (name "unconnected-(U7-~{OUTA}-Pad3)") (class "Default")
      (node (ref "U7") (pin "3") (pinfunction "~{OUTA}_3") (pintype "bidirectional"))
    )
    (net (code "245") (name "unconnected-(U7-~{OUTB}-Pad5)") (class "Default")
      (node (ref "U7") (pin "5") (pinfunction "~{OUTB}_5") (pintype "bidirectional"))
    )
    (net (code "246") (name "unconnected-(U7-~{OUTC}-Pad11)") (class "Default")
      (node (ref "U7") (pin "11") (pinfunction "~{OUTC}_11") (pintype "bidirectional"))
    )
    (net (code "247") (name "unconnected-(U7-~{OUTD}-Pad13)") (class "Default")
      (node (ref "U7") (pin "13") (pinfunction "~{OUTD}_13") (pintype "bidirectional"))
    )
    (net (code "248") (name "unconnected-(U8A-Y6-Pad9)") (class "Default")
      (node (ref "U8") (pin "9") (pinfunction "Y6_9") (pintype "output"))
    )
    (net (code "249") (name "unconnected-(U9B-~{Q}-Pad8)") (class "Default")
      (node (ref "U9") (pin "8") (pinfunction "~{Q}_8") (pintype "output"))
    )
    (net (code "250") (name "unconnected-(U11-~{OUTA}-Pad3)") (class "Default")
      (node (ref "U11") (pin "3") (pinfunction "~{OUTA}_3") (pintype "bidirectional"))
    )
    (net (code "251") (name "unconnected-(U11-~{OUTB}-Pad5)") (class "Default")
      (node (ref "U11") (pin "5") (pinfunction "~{OUTB}_5") (pintype "bidirectional"))
    )
    (net (code "252") (name "unconnected-(U11-~{OUTC}-Pad11)") (class "Default")
      (node (ref "U11") (pin "11") (pinfunction "~{OUTC}_11") (pintype "bidirectional"))
    )
    (net (code "253") (name "unconnected-(U11-~{OUTD}-Pad13)") (class "Default")
      (node (ref "U11") (pin "13") (pinfunction "~{OUTD}_13") (pintype "bidirectional"))
    )
    (net (code "254") (name "unconnected-(U14-CT1-Pad8)") (class "Default")
      (node (ref "U14") (pin "8") (pinfunction "CT1_8") (pintype "passive"))
    )
    (net (code "255") (name "unconnected-(U14-CT2-Pad9)") (class "Default")
      (node (ref "U14") (pin "9") (pinfunction "CT2_9") (pintype "passive"))
    )
    (net (code "256") (name "unconnected-(U15-RFB-Pad16)") (class "Default")
      (node (ref "U15") (pin "16") (pinfunction "RFB_16") (pintype "passive"))
    )
    (net (code "257") (name "unconnected-(U16A-5Q-Pad12)") (class "Default")
      (node (ref "U16") (pin "12") (pinfunction "5Q_12") (pintype "tri_state"))
    )
    (net (code "258") (name "unconnected-(U16A-6Q-Pad15)") (class "Default")
      (node (ref "U16") (pin "15") (pinfunction "6Q_15") (pintype "tri_state"))
    )
    (net (code "259") (name "unconnected-(U16A-7Q-Pad16)") (class "Default")
      (node (ref "U16") (pin "16") (pinfunction "7Q_16") (pintype "tri_state"))
    )
    (net (code "260") (name "unconnected-(U16A-8Q-Pad19)") (class "Default")
      (node (ref "U16") (pin "19") (pinfunction "8Q_19") (pintype "tri_state"))
    )
    (net (code "261") (name "unconnected-(U17A-Q1-Pad2)") (class "Default")
      (node (ref "U17") (pin "2") (pinfunction "Q1_2") (pintype "output"))
    )
    (net (code "262") (name "unconnected-(U17A-Q4-Pad10)") (class "Default")
      (node (ref "U17") (pin "10") (pinfunction "Q4_10") (pintype "output"))
    )
    (net (code "263") (name "unconnected-(U17A-Q5-Pad12)") (class "Default")
      (node (ref "U17") (pin "12") (pinfunction "Q5_12") (pintype "output"))
    )
    (net (code "264") (name "unconnected-(U20B-Y2-Pad10)") (class "Default")
      (node (ref "U20") (pin "10") (pinfunction "Y2_10") (pintype "output"))
    )
    (net (code "265") (name "unconnected-(U20B-Y3-Pad9)") (class "Default")
      (node (ref "U20") (pin "9") (pinfunction "Y3_9") (pintype "output"))
    )
    (net (code "266") (name "unconnected-(U21A-O-Pad12)") (class "Default")
      (node (ref "U21") (pin "12") (pinfunction "O_12") (pintype "output"))
    )
    (net (code "267") (name "unconnected-(U21B-O-Pad10)") (class "Default")
      (node (ref "U21") (pin "10") (pinfunction "O_10") (pintype "output"))
    )
    (net (code "268") (name "unconnected-(U21E-O-Pad4)") (class "Default")
      (node (ref "U21") (pin "4") (pinfunction "O_4") (pintype "output"))
    )
    (net (code "269") (name "unconnected-(U22B-Q-Pad9)") (class "Default")
      (node (ref "U22") (pin "9") (pinfunction "Q_9") (pintype "output"))
    )
    (net (code "270") (name "unconnected-(U22B-~{Q}-Pad8)") (class "Default")
      (node (ref "U22") (pin "8") (pinfunction "~{Q}_8") (pintype "output"))
    )
    (net (code "271") (name "unconnected-(U23B-~{Q}-Pad8)") (class "Default")
      (node (ref "U23") (pin "8") (pinfunction "~{Q}_8") (pintype "output"))
    )
    (net (code "272") (name "unconnected-(U24-OUTC-Pad10)") (class "Default")
      (node (ref "U24") (pin "10") (pinfunction "OUTC_10") (pintype "bidirectional"))
    )
    (net (code "273") (name "unconnected-(U24-~{OUTA}-Pad3)") (class "Default")
      (node (ref "U24") (pin "3") (pinfunction "~{OUTA}_3") (pintype "bidirectional"))
    )
    (net (code "274") (name "unconnected-(U24-~{OUTB}-Pad5)") (class "Default")
      (node (ref "U24") (pin "5") (pinfunction "~{OUTB}_5") (pintype "bidirectional"))
    )
    (net (code "275") (name "unconnected-(U24-~{OUTC}-Pad11)") (class "Default")
      (node (ref "U24") (pin "11") (pinfunction "~{OUTC}_11") (pintype "bidirectional"))
    )
    (net (code "276") (name "unconnected-(U24-~{OUTD}-Pad13)") (class "Default")
      (node (ref "U24") (pin "13") (pinfunction "~{OUTD}_13") (pintype "bidirectional"))
    )
    (net (code "277") (name "unconnected-(Y2-EN-Pad1)") (class "Default")
      (node (ref "Y2") (pin "1") (pinfunction "EN_1") (pintype "bidirectional"))
    )
    (net (code "278") (name "{slash}E") (class "Default")
      (node (ref "C62") (pin "1") (pinfunction "1_1") (pintype "passive"))
      (node (ref "R28") (pin "1") (pinfunction "1_1") (pintype "passive"))
      (node (ref "U18") (pin "5") (pinfunction "5-IN_5") (pintype "passive"))
      (node (ref "U22") (pin "6") (pinfunction "~{Q}_6") (pintype "output"))
      (node (ref "U23") (pin "2") (pinfunction "D_2") (pintype "input"))
    )
    (net (code "279") (name "{slash}EORQ") (class "Default")
      (node (ref "U18") (pin "15") (pinfunction "I/O-15_15") (pintype "passive"))
      (node (ref "U20") (pin "1") (pinfunction "G_1") (pintype "input"))
    )
    (net (code "280") (name "{slash}Q") (class "Default")
      (node (ref "U18") (pin "6") (pinfunction "6-IN_6") (pintype "passive"))
      (node (ref "U23") (pin "6") (pinfunction "~{Q}_6") (pintype "output"))
    )
    (net (code "281") (name "{slash}RAMWR") (class "Default")
      (node (ref "U18") (pin "16") (pinfunction "I/O-16_16") (pintype "passive"))
      (node (ref "W6") (pin "1") (pinfunction "1_1") (pintype "passive"))
    )
    (net (code "282") (name "{slash}RD") (class "Default")
      (node (ref "U1") (pin "2") (pinfunction "~{RD}_2") (pintype "passive"))
      (node (ref "U14") (pin "6") (pinfunction "~{RD}_6") (pintype "passive"))
      (node (ref "U18") (pin "18") (pinfunction "I/O-18_18") (pintype "passive"))
      (node (ref "U2") (pin "22") (pinfunction "~{OE}_22") (pintype "input"))
    )
    (net (code "283") (name "{slash}WR") (class "Default")
      (node (ref "U1") (pin "3") (pinfunction "~{WR}_3") (pintype "passive"))
      (node (ref "U14") (pin "5") (pinfunction "~{WR}_5") (pintype "passive"))
      (node (ref "U15") (pin "13") (pinfunction "~{WR}_13") (pintype "input"))
      (node (ref "U18") (pin "19") (pinfunction "OUT-19_19") (pintype "passive"))
      (node (ref "U2") (pin "27") (pinfunction "~{WE}_27") (pintype "input"))
    )
  )
)
